# v2.net
KiCad netlist of a schematic drawn in EAGLE
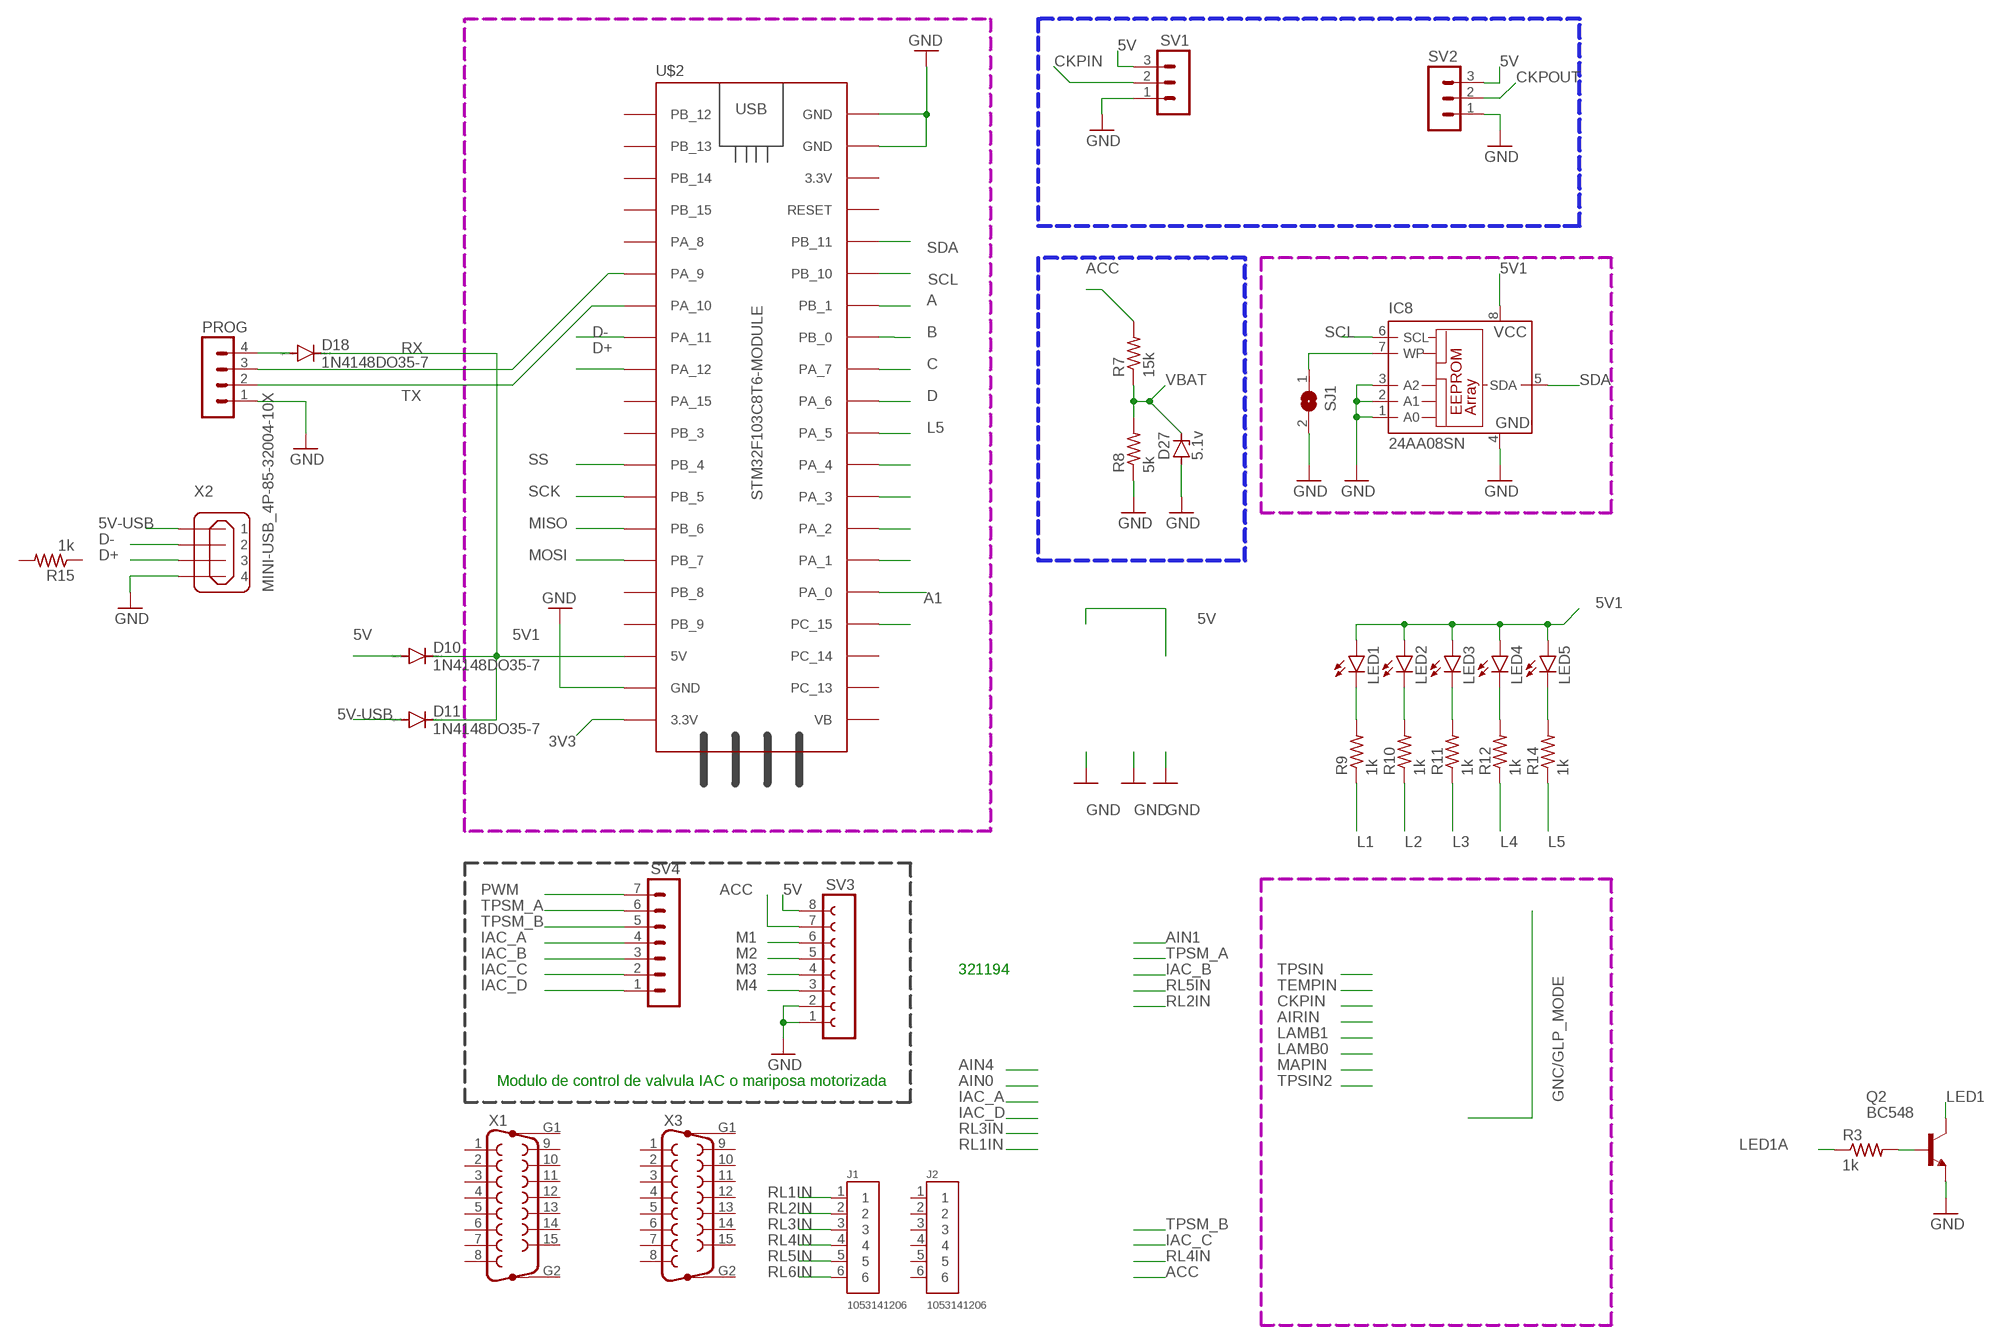
[diagram p0: schematic, sheet 1]
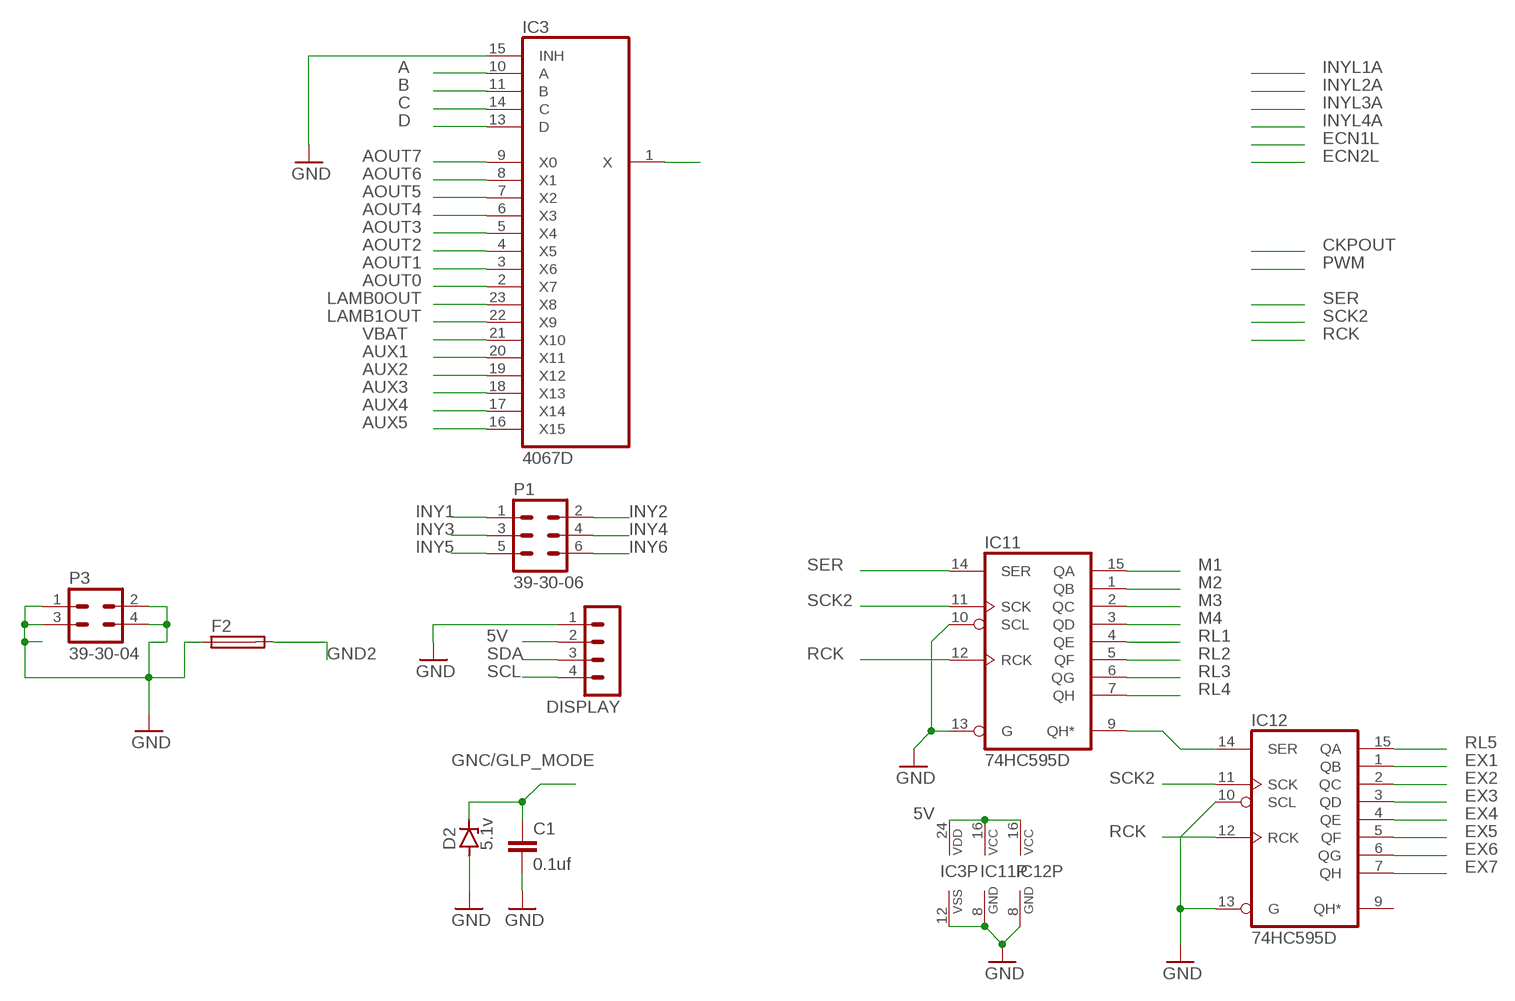
[diagram p1: schematic, sheet 2]
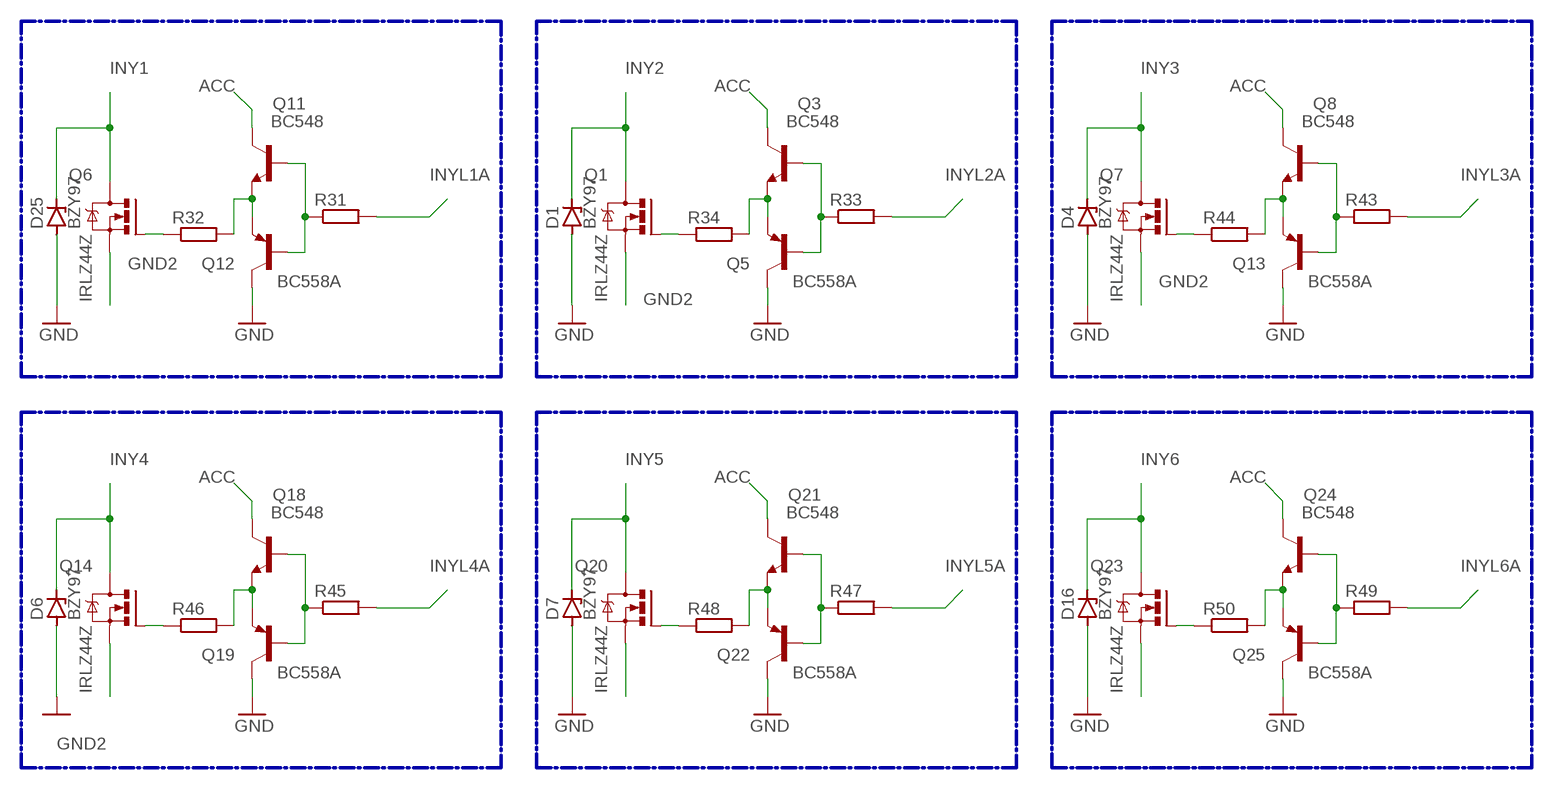
[diagram p2: schematic, sheet 3]
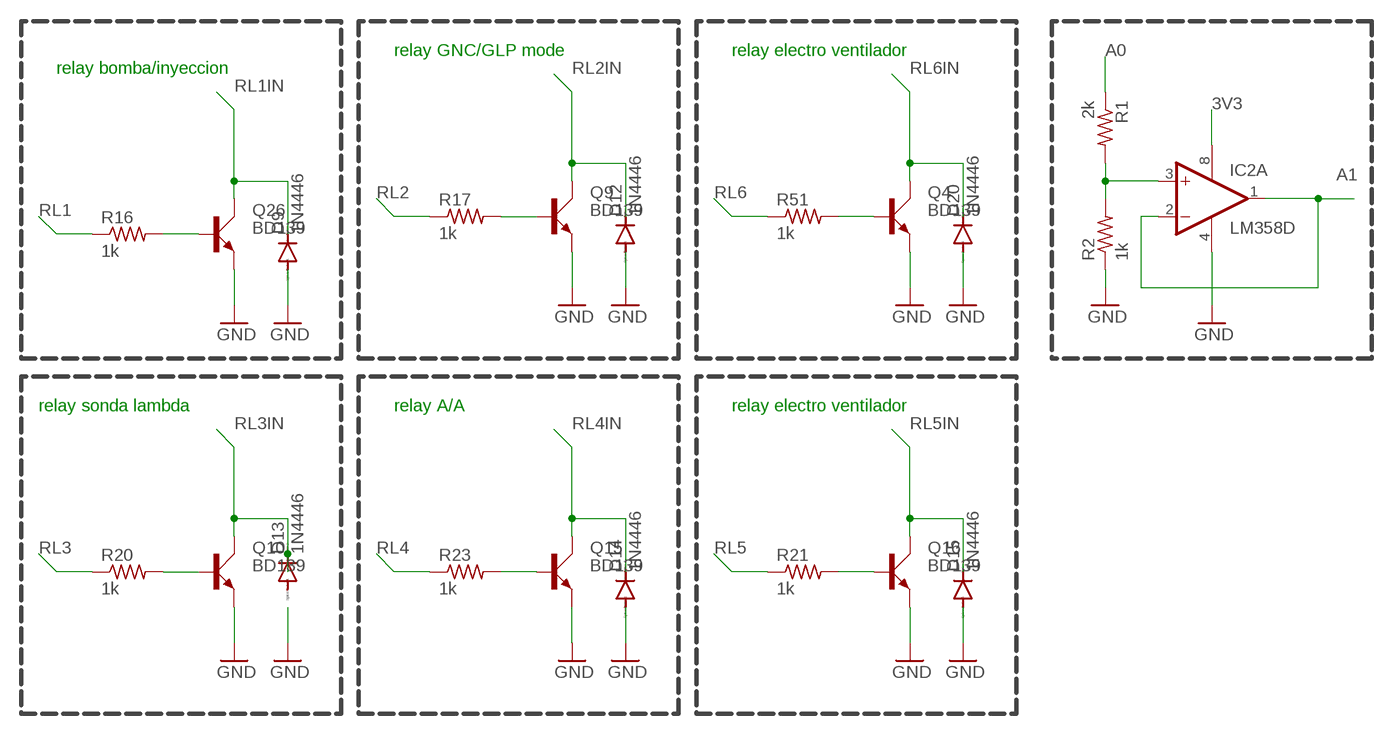
[diagram p3: schematic, sheet 4]
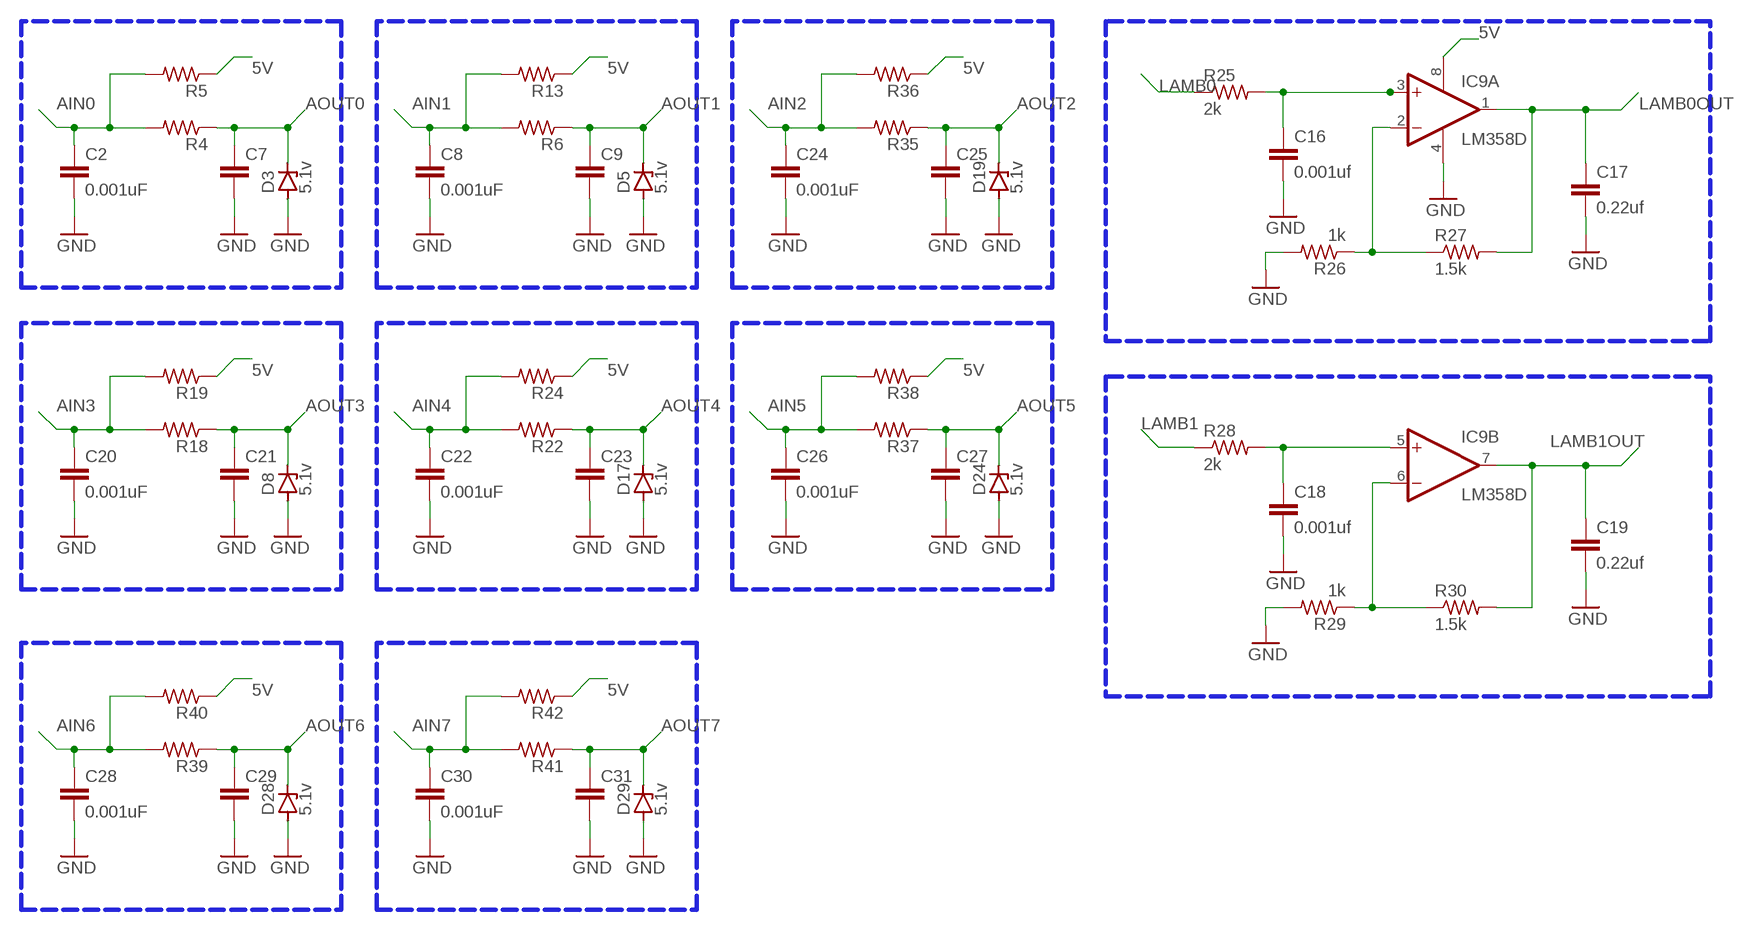
[diagram p4: schematic, sheet 5]

(export (version "E")
  (design (tool "Eeschema 10.0.6"))
  (components
    (comp (ref "D10")
      (value "1N4148DO35-7")
      (footprint "eagle-import:DO35-7")
      (libsource (lib "eagle-import") (part "1N4148DO35-7"))
    )
    (comp (ref "D11")
      (value "1N4148DO35-7")
      (footprint "eagle-import:DO35-7")
      (libsource (lib "eagle-import") (part "1N4148DO35-7"))
    )
    (comp (ref "D18")
      (value "1N4148DO35-7")
      (footprint "eagle-import:DO35-7")
      (libsource (lib "eagle-import") (part "1N4148DO35-7"))
    )
    (comp (ref "D27")
      (value "5.1v")
      (footprint "eagle-import:ZDIO-5")
      (libsource (lib "eagle-import") (part "ZENER-DIODEZD-5"))
    )
    (comp (ref "IC8")
      (value "24AA08SN")
      (footprint "eagle-import:SO-08")
      (fields (field (name "MF") "MICROCHIP") (field (name "MPN") "24AA08-I/SN"))
      (libsource (lib "eagle-import") (part "24SNAA08"))
    )
    (comp (ref "J1")
      (value "1053141206")
      (footprint "eagle-import:MOLEX_1053141206")
      (fields (field (name "MF") "Molex"))
      (libsource (lib "eagle-import") (part "1053141206"))
    )
    (comp (ref "J2")
      (value "1053141206")
      (footprint "eagle-import:MOLEX_1053141206")
      (fields (field (name "MF") "Molex"))
      (libsource (lib "eagle-import") (part "1053141206"))
    )
    (comp (ref "LED1")
      (value "LED3MM")
      (footprint "eagle-import:LED3MM")
      (libsource (lib "eagle-import") (part "LED3MM"))
    )
    (comp (ref "LED2")
      (value "LED3MM")
      (footprint "eagle-import:LED3MM")
      (libsource (lib "eagle-import") (part "LED3MM"))
    )
    (comp (ref "LED3")
      (value "LED3MM")
      (footprint "eagle-import:LED3MM")
      (libsource (lib "eagle-import") (part "LED3MM"))
    )
    (comp (ref "LED4")
      (value "LED3MM")
      (footprint "eagle-import:LED3MM")
      (libsource (lib "eagle-import") (part "LED3MM"))
    )
    (comp (ref "LED5")
      (value "LED3MM")
      (footprint "eagle-import:LED3MM")
      (libsource (lib "eagle-import") (part "LED3MM"))
    )
    (comp (ref "PROG")
      (value "MA04-1")
      (footprint "eagle-import:MA04-1")
      (libsource (lib "eagle-import") (part "MA04-1"))
    )
    (comp (ref "Q2")
      (value "BC548")
      (footprint "eagle-import:TO92-EBC")
      (libsource (lib "eagle-import") (part "BC548"))
    )
    (comp (ref "R3")
      (value "1k")
      (footprint "eagle-import:0204_5")
      (libsource (lib "eagle-import") (part "R-US_0204/5"))
    )
    (comp (ref "R7")
      (value "15k")
      (footprint "eagle-import:0204_5")
      (libsource (lib "eagle-import") (part "R-US_0204/5"))
    )
    (comp (ref "R8")
      (value "5k")
      (footprint "eagle-import:0204_5")
      (libsource (lib "eagle-import") (part "R-US_0204/5"))
    )
    (comp (ref "R9")
      (value "1k")
      (footprint "eagle-import:0204_5")
      (libsource (lib "eagle-import") (part "R-US_0204/5"))
    )
    (comp (ref "R10")
      (value "1k")
      (footprint "eagle-import:0204_5")
      (libsource (lib "eagle-import") (part "R-US_0204/5"))
    )
    (comp (ref "R11")
      (value "1k")
      (footprint "eagle-import:0204_5")
      (libsource (lib "eagle-import") (part "R-US_0204/5"))
    )
    (comp (ref "R12")
      (value "1k")
      (footprint "eagle-import:0204_5")
      (libsource (lib "eagle-import") (part "R-US_0204/5"))
    )
    (comp (ref "R14")
      (value "1k")
      (footprint "eagle-import:0204_5")
      (libsource (lib "eagle-import") (part "R-US_0204/5"))
    )
    (comp (ref "R15")
      (value "1k")
      (footprint "eagle-import:0204_5")
      (libsource (lib "eagle-import") (part "R-US_0204/5"))
    )
    (comp (ref "SJ1")
      (value "SJW")
      (footprint "eagle-import:SJW")
      (libsource (lib "eagle-import") (part "SJW"))
    )
    (comp (ref "SV1")
      (value "MA03-1")
      (footprint "eagle-import:MA03-1")
      (libsource (lib "eagle-import") (part "MA03-1"))
    )
    (comp (ref "SV2")
      (value "MA03-1")
      (footprint "eagle-import:MA03-1")
      (libsource (lib "eagle-import") (part "MA03-1"))
    )
    (comp (ref "SV3")
      (value "FE08-1")
      (footprint "eagle-import:FE08")
      (libsource (lib "eagle-import") (part "FE08-1"))
    )
    (comp (ref "SV4")
      (value "MA07-1")
      (footprint "eagle-import:MA07-1")
      (libsource (lib "eagle-import") (part "MA07-1"))
    )
    (comp (ref "U$2")
      (value "STM32F103C8T6-MODULE")
      (footprint "eagle-import:STM32F103C8T6-MODULE")
      (libsource (lib "eagle-import") (part "STM32F103C8T6-MODULE"))
    )
    (comp (ref "X1")
      (value "F15HP")
      (footprint "eagle-import:F15HP")
      (libsource (lib "eagle-import") (part "F15HP"))
    )
    (comp (ref "X2")
      (value "MINI-USB_4P-85-32004-10X")
      (footprint "eagle-import:85-32004-10X")
      (libsource (lib "eagle-import") (part "MINI-USB_4P-85-32004-10X"))
    )
    (comp (ref "X3")
      (value "F15HP")
      (footprint "eagle-import:F15HP")
      (libsource (lib "eagle-import") (part "F15HP"))
    )
    (comp (ref "C2")
      (value "0.001uF")
      (footprint "eagle-import:C025-025X050")
      (libsource (lib "eagle-import") (part "C-EU025-025X050"))
    )
    (comp (ref "C7")
      (value "C-EU025-025X050")
      (footprint "eagle-import:C025-025X050")
      (libsource (lib "eagle-import") (part "C-EU025-025X050"))
    )
    (comp (ref "C8")
      (value "0.001uF")
      (footprint "eagle-import:C025-025X050")
      (libsource (lib "eagle-import") (part "C-EU025-025X050"))
    )
    (comp (ref "C9")
      (value "C-EU025-025X050")
      (footprint "eagle-import:C025-025X050")
      (libsource (lib "eagle-import") (part "C-EU025-025X050"))
    )
    (comp (ref "C16")
      (value "0.001uf")
      (footprint "eagle-import:C025-025X050")
      (libsource (lib "eagle-import") (part "C-EU025-025X050"))
    )
    (comp (ref "C17")
      (value "0.22uf")
      (footprint "eagle-import:C025-025X050")
      (libsource (lib "eagle-import") (part "C-EU025-025X050"))
    )
    (comp (ref "C18")
      (value "0.001uf")
      (footprint "eagle-import:C025-025X050")
      (libsource (lib "eagle-import") (part "C-EU025-025X050"))
    )
    (comp (ref "C19")
      (value "0.22uf")
      (footprint "eagle-import:C025-025X050")
      (libsource (lib "eagle-import") (part "C-EU025-025X050"))
    )
    (comp (ref "C20")
      (value "0.001uF")
      (footprint "eagle-import:C025-025X050")
      (libsource (lib "eagle-import") (part "C-EU025-025X050"))
    )
    (comp (ref "C21")
      (value "C-EU025-025X050")
      (footprint "eagle-import:C025-025X050")
      (libsource (lib "eagle-import") (part "C-EU025-025X050"))
    )
    (comp (ref "C22")
      (value "0.001uF")
      (footprint "eagle-import:C025-025X050")
      (libsource (lib "eagle-import") (part "C-EU025-025X050"))
    )
    (comp (ref "C23")
      (value "C-EU025-025X050")
      (footprint "eagle-import:C025-025X050")
      (libsource (lib "eagle-import") (part "C-EU025-025X050"))
    )
    (comp (ref "C24")
      (value "0.001uF")
      (footprint "eagle-import:C025-025X050")
      (libsource (lib "eagle-import") (part "C-EU025-025X050"))
    )
    (comp (ref "C25")
      (value "C-EU025-025X050")
      (footprint "eagle-import:C025-025X050")
      (libsource (lib "eagle-import") (part "C-EU025-025X050"))
    )
    (comp (ref "C26")
      (value "0.001uF")
      (footprint "eagle-import:C025-025X050")
      (libsource (lib "eagle-import") (part "C-EU025-025X050"))
    )
    (comp (ref "C27")
      (value "C-EU025-025X050")
      (footprint "eagle-import:C025-025X050")
      (libsource (lib "eagle-import") (part "C-EU025-025X050"))
    )
    (comp (ref "C28")
      (value "0.001uF")
      (footprint "eagle-import:C025-025X050")
      (libsource (lib "eagle-import") (part "C-EU025-025X050"))
    )
    (comp (ref "C29")
      (value "C-EU025-025X050")
      (footprint "eagle-import:C025-025X050")
      (libsource (lib "eagle-import") (part "C-EU025-025X050"))
    )
    (comp (ref "C30")
      (value "0.001uF")
      (footprint "eagle-import:C025-025X050")
      (libsource (lib "eagle-import") (part "C-EU025-025X050"))
    )
    (comp (ref "C31")
      (value "C-EU025-025X050")
      (footprint "eagle-import:C025-025X050")
      (libsource (lib "eagle-import") (part "C-EU025-025X050"))
    )
    (comp (ref "D3")
      (value "5.1v")
      (footprint "eagle-import:ZDIO-5")
      (libsource (lib "eagle-import") (part "ZENER-DIODEZD-5"))
    )
    (comp (ref "D5")
      (value "5.1v")
      (footprint "eagle-import:ZDIO-5")
      (libsource (lib "eagle-import") (part "ZENER-DIODEZD-5"))
    )
    (comp (ref "D8")
      (value "5.1v")
      (footprint "eagle-import:ZDIO-5")
      (libsource (lib "eagle-import") (part "ZENER-DIODEZD-5"))
    )
    (comp (ref "D17")
      (value "5.1v")
      (footprint "eagle-import:ZDIO-5")
      (libsource (lib "eagle-import") (part "ZENER-DIODEZD-5"))
    )
    (comp (ref "D19")
      (value "5.1v")
      (footprint "eagle-import:ZDIO-5")
      (libsource (lib "eagle-import") (part "ZENER-DIODEZD-5"))
    )
    (comp (ref "D24")
      (value "5.1v")
      (footprint "eagle-import:ZDIO-5")
      (libsource (lib "eagle-import") (part "ZENER-DIODEZD-5"))
    )
    (comp (ref "D28")
      (value "5.1v")
      (footprint "eagle-import:ZDIO-5")
      (libsource (lib "eagle-import") (part "ZENER-DIODEZD-5"))
    )
    (comp (ref "D29")
      (value "5.1v")
      (footprint "eagle-import:ZDIO-5")
      (libsource (lib "eagle-import") (part "ZENER-DIODEZD-5"))
    )
    (comp (ref "IC9")
      (value "LM358D")
      (footprint "eagle-import:SO08")
      (libsource (lib "eagle-import") (part "LM358D"))
    )
    (comp (ref "R4")
      (value "R-US_0204/5")
      (footprint "eagle-import:0204_5")
      (libsource (lib "eagle-import") (part "R-US_0204/5"))
    )
    (comp (ref "R5")
      (value "R-US_0204/5")
      (footprint "eagle-import:0204_5")
      (libsource (lib "eagle-import") (part "R-US_0204/5"))
    )
    (comp (ref "R6")
      (value "R-US_0204/5")
      (footprint "eagle-import:0204_5")
      (libsource (lib "eagle-import") (part "R-US_0204/5"))
    )
    (comp (ref "R13")
      (value "R-US_0204/5")
      (footprint "eagle-import:0204_5")
      (libsource (lib "eagle-import") (part "R-US_0204/5"))
    )
    (comp (ref "R18")
      (value "R-US_0204/5")
      (footprint "eagle-import:0204_5")
      (libsource (lib "eagle-import") (part "R-US_0204/5"))
    )
    (comp (ref "R19")
      (value "R-US_0204/5")
      (footprint "eagle-import:0204_5")
      (libsource (lib "eagle-import") (part "R-US_0204/5"))
    )
    (comp (ref "R22")
      (value "R-US_0204/5")
      (footprint "eagle-import:0204_5")
      (libsource (lib "eagle-import") (part "R-US_0204/5"))
    )
    (comp (ref "R24")
      (value "R-US_0204/5")
      (footprint "eagle-import:0204_5")
      (libsource (lib "eagle-import") (part "R-US_0204/5"))
    )
    (comp (ref "R25")
      (value "2k")
      (footprint "eagle-import:0204_5")
      (libsource (lib "eagle-import") (part "R-US_0204/5"))
    )
    (comp (ref "R26")
      (value "1k")
      (footprint "eagle-import:0204_5")
      (libsource (lib "eagle-import") (part "R-US_0204/5"))
    )
    (comp (ref "R27")
      (value "1.5k")
      (footprint "eagle-import:0204_5")
      (libsource (lib "eagle-import") (part "R-US_0204/5"))
    )
    (comp (ref "R28")
      (value "2k")
      (footprint "eagle-import:0204_5")
      (libsource (lib "eagle-import") (part "R-US_0204/5"))
    )
    (comp (ref "R29")
      (value "1k")
      (footprint "eagle-import:0204_5")
      (libsource (lib "eagle-import") (part "R-US_0204/5"))
    )
    (comp (ref "R30")
      (value "1.5k")
      (footprint "eagle-import:0204_5")
      (libsource (lib "eagle-import") (part "R-US_0204/5"))
    )
    (comp (ref "R35")
      (value "R-US_0204/5")
      (footprint "eagle-import:0204_5")
      (libsource (lib "eagle-import") (part "R-US_0204/5"))
    )
    (comp (ref "R36")
      (value "R-US_0204/5")
      (footprint "eagle-import:0204_5")
      (libsource (lib "eagle-import") (part "R-US_0204/5"))
    )
    (comp (ref "R37")
      (value "R-US_0204/5")
      (footprint "eagle-import:0204_5")
      (libsource (lib "eagle-import") (part "R-US_0204/5"))
    )
    (comp (ref "R38")
      (value "R-US_0204/5")
      (footprint "eagle-import:0204_5")
      (libsource (lib "eagle-import") (part "R-US_0204/5"))
    )
    (comp (ref "R39")
      (value "R-US_0204/5")
      (footprint "eagle-import:0204_5")
      (libsource (lib "eagle-import") (part "R-US_0204/5"))
    )
    (comp (ref "R40")
      (value "R-US_0204/5")
      (footprint "eagle-import:0204_5")
      (libsource (lib "eagle-import") (part "R-US_0204/5"))
    )
    (comp (ref "R41")
      (value "R-US_0204/5")
      (footprint "eagle-import:0204_5")
      (libsource (lib "eagle-import") (part "R-US_0204/5"))
    )
    (comp (ref "R42")
      (value "R-US_0204/5")
      (footprint "eagle-import:0204_5")
      (libsource (lib "eagle-import") (part "R-US_0204/5"))
    )
    (comp (ref "D9")
      (value "1N4446")
      (footprint "eagle-import:DO35-10")
      (libsource (lib "eagle-import") (part "1N4446"))
    )
    (comp (ref "D12")
      (value "1N4446")
      (footprint "eagle-import:DO35-10")
      (libsource (lib "eagle-import") (part "1N4446"))
    )
    (comp (ref "D13")
      (value "1N4446")
      (footprint "eagle-import:DO35-10")
      (libsource (lib "eagle-import") (part "1N4446"))
    )
    (comp (ref "D14")
      (value "1N4446")
      (footprint "eagle-import:DO35-10")
      (libsource (lib "eagle-import") (part "1N4446"))
    )
    (comp (ref "D15")
      (value "1N4446")
      (footprint "eagle-import:DO35-10")
      (libsource (lib "eagle-import") (part "1N4446"))
    )
    (comp (ref "D20")
      (value "1N4446")
      (footprint "eagle-import:DO35-10")
      (libsource (lib "eagle-import") (part "1N4446"))
    )
    (comp (ref "IC2")
      (value "LM358D")
      (footprint "eagle-import:SO08")
      (libsource (lib "eagle-import") (part "LM358D"))
    )
    (comp (ref "Q4")
      (value "BD139")
      (footprint "eagle-import:TO126AV")
      (libsource (lib "eagle-import") (part "BD139"))
    )
    (comp (ref "Q9")
      (value "BD139")
      (footprint "eagle-import:TO126AV")
      (libsource (lib "eagle-import") (part "BD139"))
    )
    (comp (ref "Q10")
      (value "BD139")
      (footprint "eagle-import:TO126AV")
      (libsource (lib "eagle-import") (part "BD139"))
    )
    (comp (ref "Q15")
      (value "BD139")
      (footprint "eagle-import:TO126AV")
      (libsource (lib "eagle-import") (part "BD139"))
    )
    (comp (ref "Q16")
      (value "BD139")
      (footprint "eagle-import:TO126AV")
      (libsource (lib "eagle-import") (part "BD139"))
    )
    (comp (ref "Q26")
      (value "BD139")
      (footprint "eagle-import:TO126AV")
      (libsource (lib "eagle-import") (part "BD139"))
    )
    (comp (ref "R1")
      (value "2k")
      (footprint "eagle-import:0204_5")
      (libsource (lib "eagle-import") (part "R-US_0204/5"))
    )
    (comp (ref "R2")
      (value "1k")
      (footprint "eagle-import:0204_5")
      (libsource (lib "eagle-import") (part "R-US_0204/5"))
    )
    (comp (ref "R16")
      (value "1k")
      (footprint "eagle-import:0204_5")
      (libsource (lib "eagle-import") (part "R-US_0204/5"))
    )
    (comp (ref "R17")
      (value "1k")
      (footprint "eagle-import:0204_5")
      (libsource (lib "eagle-import") (part "R-US_0204/5"))
    )
    (comp (ref "R20")
      (value "1k")
      (footprint "eagle-import:0204_5")
      (libsource (lib "eagle-import") (part "R-US_0204/5"))
    )
    (comp (ref "R21")
      (value "1k")
      (footprint "eagle-import:0204_5")
      (libsource (lib "eagle-import") (part "R-US_0204/5"))
    )
    (comp (ref "R23")
      (value "1k")
      (footprint "eagle-import:0204_5")
      (libsource (lib "eagle-import") (part "R-US_0204/5"))
    )
    (comp (ref "R51")
      (value "1k")
      (footprint "eagle-import:0204_5")
      (libsource (lib "eagle-import") (part "R-US_0204/5"))
    )
    (comp (ref "D1")
      (value "BZY97")
      (footprint "eagle-import:F126Z12")
      (libsource (lib "eagle-import") (part "BZY97"))
    )
    (comp (ref "D4")
      (value "BZY97")
      (footprint "eagle-import:F126Z12")
      (libsource (lib "eagle-import") (part "BZY97"))
    )
    (comp (ref "D6")
      (value "BZY97")
      (footprint "eagle-import:F126Z12")
      (libsource (lib "eagle-import") (part "BZY97"))
    )
    (comp (ref "D7")
      (value "BZY97")
      (footprint "eagle-import:F126Z12")
      (libsource (lib "eagle-import") (part "BZY97"))
    )
    (comp (ref "D16")
      (value "BZY97")
      (footprint "eagle-import:F126Z12")
      (libsource (lib "eagle-import") (part "BZY97"))
    )
    (comp (ref "D25")
      (value "BZY97")
      (footprint "eagle-import:F126Z12")
      (libsource (lib "eagle-import") (part "BZY97"))
    )
    (comp (ref "Q1")
      (value "IRLZ44Z")
      (footprint "eagle-import:TO220BH")
      (libsource (lib "eagle-import") (part "IRLZ44Z"))
    )
    (comp (ref "Q3")
      (value "BC548")
      (footprint "eagle-import:TO92-EBC")
      (libsource (lib "eagle-import") (part "BC548"))
    )
    (comp (ref "Q5")
      (value "BC558A")
      (footprint "eagle-import:TO92-EBC")
      (libsource (lib "eagle-import") (part "BC558A"))
    )
    (comp (ref "Q6")
      (value "IRLZ44Z")
      (footprint "eagle-import:TO220BH")
      (libsource (lib "eagle-import") (part "IRLZ44Z"))
    )
    (comp (ref "Q7")
      (value "IRLZ44Z")
      (footprint "eagle-import:TO220BH")
      (libsource (lib "eagle-import") (part "IRLZ44Z"))
    )
    (comp (ref "Q8")
      (value "BC548")
      (footprint "eagle-import:TO92-EBC")
      (libsource (lib "eagle-import") (part "BC548"))
    )
    (comp (ref "Q11")
      (value "BC548")
      (footprint "eagle-import:TO92-EBC")
      (libsource (lib "eagle-import") (part "BC548"))
    )
    (comp (ref "Q12")
      (value "BC558A")
      (footprint "eagle-import:TO92-EBC")
      (libsource (lib "eagle-import") (part "BC558A"))
    )
    (comp (ref "Q13")
      (value "BC558A")
      (footprint "eagle-import:TO92-EBC")
      (libsource (lib "eagle-import") (part "BC558A"))
    )
    (comp (ref "Q14")
      (value "IRLZ44Z")
      (footprint "eagle-import:TO220BH")
      (libsource (lib "eagle-import") (part "IRLZ44Z"))
    )
    (comp (ref "Q18")
      (value "BC548")
      (footprint "eagle-import:TO92-EBC")
      (libsource (lib "eagle-import") (part "BC548"))
    )
    (comp (ref "Q19")
      (value "BC558A")
      (footprint "eagle-import:TO92-EBC")
      (libsource (lib "eagle-import") (part "BC558A"))
    )
    (comp (ref "Q20")
      (value "IRLZ44Z")
      (footprint "eagle-import:TO220BH")
      (libsource (lib "eagle-import") (part "IRLZ44Z"))
    )
    (comp (ref "Q21")
      (value "BC548")
      (footprint "eagle-import:TO92-EBC")
      (libsource (lib "eagle-import") (part "BC548"))
    )
    (comp (ref "Q22")
      (value "BC558A")
      (footprint "eagle-import:TO92-EBC")
      (libsource (lib "eagle-import") (part "BC558A"))
    )
    (comp (ref "Q23")
      (value "IRLZ44Z")
      (footprint "eagle-import:TO220BH")
      (libsource (lib "eagle-import") (part "IRLZ44Z"))
    )
    (comp (ref "Q24")
      (value "BC548")
      (footprint "eagle-import:TO92-EBC")
      (libsource (lib "eagle-import") (part "BC548"))
    )
    (comp (ref "Q25")
      (value "BC558A")
      (footprint "eagle-import:TO92-EBC")
      (libsource (lib "eagle-import") (part "BC558A"))
    )
    (comp (ref "R31")
      (value "R-EU_0207/10")
      (footprint "eagle-import:0207_10")
      (libsource (lib "eagle-import") (part "R-EU_0207/10"))
    )
    (comp (ref "R32")
      (value "R-EU_0207/10")
      (footprint "eagle-import:0207_10")
      (libsource (lib "eagle-import") (part "R-EU_0207/10"))
    )
    (comp (ref "R33")
      (value "R-EU_0207/10")
      (footprint "eagle-import:0207_10")
      (libsource (lib "eagle-import") (part "R-EU_0207/10"))
    )
    (comp (ref "R34")
      (value "R-EU_0207/10")
      (footprint "eagle-import:0207_10")
      (libsource (lib "eagle-import") (part "R-EU_0207/10"))
    )
    (comp (ref "R43")
      (value "R-EU_0207/10")
      (footprint "eagle-import:0207_10")
      (libsource (lib "eagle-import") (part "R-EU_0207/10"))
    )
    (comp (ref "R44")
      (value "R-EU_0207/10")
      (footprint "eagle-import:0207_10")
      (libsource (lib "eagle-import") (part "R-EU_0207/10"))
    )
    (comp (ref "R45")
      (value "R-EU_0207/10")
      (footprint "eagle-import:0207_10")
      (libsource (lib "eagle-import") (part "R-EU_0207/10"))
    )
    (comp (ref "R46")
      (value "R-EU_0207/10")
      (footprint "eagle-import:0207_10")
      (libsource (lib "eagle-import") (part "R-EU_0207/10"))
    )
    (comp (ref "R47")
      (value "R-EU_0207/10")
      (footprint "eagle-import:0207_10")
      (libsource (lib "eagle-import") (part "R-EU_0207/10"))
    )
    (comp (ref "R48")
      (value "R-EU_0207/10")
      (footprint "eagle-import:0207_10")
      (libsource (lib "eagle-import") (part "R-EU_0207/10"))
    )
    (comp (ref "R49")
      (value "R-EU_0207/10")
      (footprint "eagle-import:0207_10")
      (libsource (lib "eagle-import") (part "R-EU_0207/10"))
    )
    (comp (ref "R50")
      (value "R-EU_0207/10")
      (footprint "eagle-import:0207_10")
      (libsource (lib "eagle-import") (part "R-EU_0207/10"))
    )
    (comp (ref "C1")
      (value "0.1uf")
      (footprint "eagle-import:C025-025X050")
      (libsource (lib "eagle-import") (part "C-EU025-025X050"))
    )
    (comp (ref "D2")
      (value "5.1v")
      (footprint "eagle-import:ZDIO-5")
      (libsource (lib "eagle-import") (part "ZENER-DIODEZD-5"))
    )
    (comp (ref "DISPLAY")
      (value "MA04-1")
      (footprint "eagle-import:MA04-1")
      (libsource (lib "eagle-import") (part "MA04-1"))
    )
    (comp (ref "F2")
      (value "TE5")
      (footprint "eagle-import:TE5")
      (libsource (lib "eagle-import") (part "TE5"))
    )
    (comp (ref "IC3")
      (value "4067D")
      (footprint "eagle-import:SO24W")
      (libsource (lib "eagle-import") (part "4067D"))
    )
    (comp (ref "IC11")
      (value "74HC595D")
      (footprint "eagle-import:SO16")
      (libsource (lib "eagle-import") (part "74595DHC"))
    )
    (comp (ref "IC12")
      (value "74HC595D")
      (footprint "eagle-import:SO16")
      (libsource (lib "eagle-import") (part "74595DHC"))
    )
    (comp (ref "P1")
      (value "39-30-06")
      (footprint "eagle-import:39-30-_06_")
      (libsource (lib "eagle-import") (part "39-30-?06?"))
    )
    (comp (ref "P3")
      (value "39-30-04")
      (footprint "eagle-import:39-30-_04_")
      (libsource (lib "eagle-import") (part "39-30-?04?"))
    )
  )
  (nets
    (net (code "3") (name "3V3") (class "Default")
      (node (ref "IC2") (pin "8") (pinfunction "V+_8") (pintype "power_in"))
      (node (ref "U$2") (pin "3.3V_1") (pinfunction "3.3V_3.3V_1") (pintype "bidirectional"))
    )
    (net (code "4") (name "5V") (class "Default")
      (node (ref "D10") (pin "A") (pinfunction "A_A") (pintype "passive"))
      (node (ref "DISPLAY") (pin "2") (pinfunction "2_2") (pintype "passive"))
      (node (ref "IC11") (pin "16") (pinfunction "VCC_16") (pintype "power_in"))
      (node (ref "IC12") (pin "16") (pinfunction "VCC_16") (pintype "power_in"))
      (node (ref "IC3") (pin "24") (pinfunction "VDD_24") (pintype "power_in"))
      (node (ref "IC9") (pin "8") (pinfunction "V+_8") (pintype "power_in"))
      (node (ref "R13") (pin "1") (pinfunction "1_1") (pintype "passive"))
      (node (ref "R19") (pin "1") (pinfunction "1_1") (pintype "passive"))
      (node (ref "R24") (pin "1") (pinfunction "1_1") (pintype "passive"))
      (node (ref "R36") (pin "1") (pinfunction "1_1") (pintype "passive"))
      (node (ref "R38") (pin "1") (pinfunction "1_1") (pintype "passive"))
      (node (ref "R40") (pin "1") (pinfunction "1_1") (pintype "passive"))
      (node (ref "R42") (pin "1") (pinfunction "1_1") (pintype "passive"))
      (node (ref "R5") (pin "1") (pinfunction "1_1") (pintype "passive"))
      (node (ref "SV1") (pin "3") (pinfunction "3_3") (pintype "passive"))
      (node (ref "SV2") (pin "3") (pinfunction "3_3") (pintype "passive"))
      (node (ref "SV3") (pin "8") (pinfunction "8_8") (pintype "passive"))
    )
    (net (code "5") (name "5V-USB") (class "Default")
      (node (ref "D11") (pin "A") (pinfunction "A_A") (pintype "passive"))
      (node (ref "X2") (pin "1") (pinfunction "1_1") (pintype "passive"))
    )
    (net (code "6") (name "5V1") (class "Default")
      (node (ref "D10") (pin "C") (pinfunction "C_C") (pintype "passive"))
      (node (ref "D11") (pin "C") (pinfunction "C_C") (pintype "passive"))
      (node (ref "D18") (pin "C") (pinfunction "C_C") (pintype "passive"))
      (node (ref "IC8") (pin "8") (pinfunction "VCC_8") (pintype "power_in"))
      (node (ref "LED1") (pin "A") (pinfunction "A_A") (pintype "passive"))
      (node (ref "LED2") (pin "A") (pinfunction "A_A") (pintype "passive"))
      (node (ref "LED3") (pin "A") (pinfunction "A_A") (pintype "passive"))
      (node (ref "LED4") (pin "A") (pinfunction "A_A") (pintype "passive"))
      (node (ref "LED5") (pin "A") (pinfunction "A_A") (pintype "passive"))
      (node (ref "U$2") (pin "5V") (pinfunction "5V_5V") (pintype "bidirectional"))
    )
    (net (code "7") (name "A") (class "Default")
      (node (ref "IC3") (pin "10") (pinfunction "A_10") (pintype "input"))
      (node (ref "U$2") (pin "PB_1") (pinfunction "PB_1_PB_1") (pintype "bidirectional"))
    )
    (net (code "8") (name "A0") (class "Default")
      (node (ref "IC3") (pin "1") (pinfunction "X_1") (pintype "output"))
      (node (ref "R1") (pin "1") (pinfunction "1_1") (pintype "passive"))
    )
    (net (code "9") (name "A1") (class "Default")
      (node (ref "IC2") (pin "1") (pinfunction "OUT_1") (pintype "output"))
      (node (ref "IC2") (pin "2") (pinfunction "-IN_2") (pintype "input"))
      (node (ref "U$2") (pin "PA_0") (pinfunction "PA_0_PA_0") (pintype "bidirectional"))
    )
    (net (code "10") (name "ACC") (class "Default")
      (node (ref "Q11") (pin "C") (pinfunction "C_C") (pintype "passive"))
      (node (ref "Q18") (pin "C") (pinfunction "C_C") (pintype "passive"))
      (node (ref "Q21") (pin "C") (pinfunction "C_C") (pintype "passive"))
      (node (ref "Q24") (pin "C") (pinfunction "C_C") (pintype "passive"))
      (node (ref "Q3") (pin "C") (pinfunction "C_C") (pintype "passive"))
      (node (ref "Q8") (pin "C") (pinfunction "C_C") (pintype "passive"))
      (node (ref "R7") (pin "2") (pinfunction "2_2") (pintype "passive"))
      (node (ref "SV3") (pin "7") (pinfunction "7_7") (pintype "passive"))
    )
    (net (code "11") (name "AIN0") (class "Default")
      (node (ref "C2") (pin "1") (pinfunction "1_1") (pintype "passive"))
      (node (ref "R4") (pin "2") (pinfunction "2_2") (pintype "passive"))
      (node (ref "R5") (pin "2") (pinfunction "2_2") (pintype "passive"))
    )
    (net (code "12") (name "AIN1") (class "Default")
      (node (ref "C8") (pin "1") (pinfunction "1_1") (pintype "passive"))
      (node (ref "R13") (pin "2") (pinfunction "2_2") (pintype "passive"))
      (node (ref "R6") (pin "2") (pinfunction "2_2") (pintype "passive"))
    )
    (net (code "13") (name "AIN2") (class "Default")
      (node (ref "C24") (pin "1") (pinfunction "1_1") (pintype "passive"))
      (node (ref "R35") (pin "2") (pinfunction "2_2") (pintype "passive"))
      (node (ref "R36") (pin "2") (pinfunction "2_2") (pintype "passive"))
    )
    (net (code "14") (name "AIN3") (class "Default")
      (node (ref "C20") (pin "1") (pinfunction "1_1") (pintype "passive"))
      (node (ref "R18") (pin "2") (pinfunction "2_2") (pintype "passive"))
      (node (ref "R19") (pin "2") (pinfunction "2_2") (pintype "passive"))
    )
    (net (code "15") (name "AIN4") (class "Default")
      (node (ref "C22") (pin "1") (pinfunction "1_1") (pintype "passive"))
      (node (ref "R22") (pin "2") (pinfunction "2_2") (pintype "passive"))
      (node (ref "R24") (pin "2") (pinfunction "2_2") (pintype "passive"))
    )
    (net (code "16") (name "AIN5") (class "Default")
      (node (ref "C26") (pin "1") (pinfunction "1_1") (pintype "passive"))
      (node (ref "R37") (pin "2") (pinfunction "2_2") (pintype "passive"))
      (node (ref "R38") (pin "2") (pinfunction "2_2") (pintype "passive"))
    )
    (net (code "17") (name "AIN6") (class "Default")
      (node (ref "C28") (pin "1") (pinfunction "1_1") (pintype "passive"))
      (node (ref "R39") (pin "2") (pinfunction "2_2") (pintype "passive"))
      (node (ref "R40") (pin "2") (pinfunction "2_2") (pintype "passive"))
    )
    (net (code "18") (name "AIN7") (class "Default")
      (node (ref "C30") (pin "1") (pinfunction "1_1") (pintype "passive"))
      (node (ref "R41") (pin "2") (pinfunction "2_2") (pintype "passive"))
      (node (ref "R42") (pin "2") (pinfunction "2_2") (pintype "passive"))
    )
    (net (code "20") (name "AOUT0") (class "Default")
      (node (ref "C7") (pin "1") (pinfunction "1_1") (pintype "passive"))
      (node (ref "D3") (pin "C") (pinfunction "C_C") (pintype "passive"))
      (node (ref "IC3") (pin "2") (pinfunction "X7_2") (pintype "input"))
      (node (ref "R4") (pin "1") (pinfunction "1_1") (pintype "passive"))
    )
    (net (code "21") (name "AOUT1") (class "Default")
      (node (ref "C9") (pin "1") (pinfunction "1_1") (pintype "passive"))
      (node (ref "D5") (pin "C") (pinfunction "C_C") (pintype "passive"))
      (node (ref "IC3") (pin "3") (pinfunction "X6_3") (pintype "input"))
      (node (ref "R6") (pin "1") (pinfunction "1_1") (pintype "passive"))
    )
    (net (code "22") (name "AOUT2") (class "Default")
      (node (ref "C25") (pin "1") (pinfunction "1_1") (pintype "passive"))
      (node (ref "D19") (pin "C") (pinfunction "C_C") (pintype "passive"))
      (node (ref "IC3") (pin "4") (pinfunction "X5_4") (pintype "input"))
      (node (ref "R35") (pin "1") (pinfunction "1_1") (pintype "passive"))
    )
    (net (code "23") (name "AOUT3") (class "Default")
      (node (ref "C21") (pin "1") (pinfunction "1_1") (pintype "passive"))
      (node (ref "D8") (pin "C") (pinfunction "C_C") (pintype "passive"))
      (node (ref "IC3") (pin "5") (pinfunction "X4_5") (pintype "input"))
      (node (ref "R18") (pin "1") (pinfunction "1_1") (pintype "passive"))
    )
    (net (code "24") (name "AOUT4") (class "Default")
      (node (ref "C23") (pin "1") (pinfunction "1_1") (pintype "passive"))
      (node (ref "D17") (pin "C") (pinfunction "C_C") (pintype "passive"))
      (node (ref "IC3") (pin "6") (pinfunction "X3_6") (pintype "input"))
      (node (ref "R22") (pin "1") (pinfunction "1_1") (pintype "passive"))
    )
    (net (code "25") (name "AOUT5") (class "Default")
      (node (ref "C27") (pin "1") (pinfunction "1_1") (pintype "passive"))
      (node (ref "D24") (pin "C") (pinfunction "C_C") (pintype "passive"))
      (node (ref "IC3") (pin "7") (pinfunction "X2_7") (pintype "input"))
      (node (ref "R37") (pin "1") (pinfunction "1_1") (pintype "passive"))
    )
    (net (code "26") (name "AOUT6") (class "Default")
      (node (ref "C29") (pin "1") (pinfunction "1_1") (pintype "passive"))
      (node (ref "D28") (pin "C") (pinfunction "C_C") (pintype "passive"))
      (node (ref "IC3") (pin "8") (pinfunction "X1_8") (pintype "input"))
      (node (ref "R39") (pin "1") (pinfunction "1_1") (pintype "passive"))
    )
    (net (code "27") (name "AOUT7") (class "Default")
      (node (ref "C31") (pin "1") (pinfunction "1_1") (pintype "passive"))
      (node (ref "D29") (pin "C") (pinfunction "C_C") (pintype "passive"))
      (node (ref "IC3") (pin "9") (pinfunction "X0_9") (pintype "input"))
      (node (ref "R41") (pin "1") (pinfunction "1_1") (pintype "passive"))
    )
    (net (code "28") (name "AUX1") (class "Default")
      (node (ref "IC3") (pin "20") (pinfunction "X11_20") (pintype "input"))
    )
    (net (code "29") (name "AUX2") (class "Default")
      (node (ref "IC3") (pin "19") (pinfunction "X12_19") (pintype "input"))
    )
    (net (code "30") (name "AUX3") (class "Default")
      (node (ref "IC3") (pin "18") (pinfunction "X13_18") (pintype "input"))
    )
    (net (code "31") (name "AUX4") (class "Default")
      (node (ref "IC3") (pin "17") (pinfunction "X14_17") (pintype "input"))
    )
    (net (code "32") (name "AUX5") (class "Default")
      (node (ref "IC3") (pin "16") (pinfunction "X15_16") (pintype "input"))
    )
    (net (code "33") (name "B") (class "Default")
      (node (ref "IC3") (pin "11") (pinfunction "B_11") (pintype "input"))
      (node (ref "U$2") (pin "PB_0") (pinfunction "PB_0_PB_0") (pintype "bidirectional"))
    )
    (net (code "34") (name "C") (class "Default")
      (node (ref "IC3") (pin "14") (pinfunction "C_14") (pintype "input"))
      (node (ref "U$2") (pin "PA_7") (pinfunction "PA_7_PA_7") (pintype "bidirectional"))
    )
    (net (code "35") (name "CKPIN") (class "Default")
      (node (ref "SV1") (pin "2") (pinfunction "2_2") (pintype "passive"))
    )
    (net (code "36") (name "CKPOUT") (class "Default")
      (node (ref "SV2") (pin "2") (pinfunction "2_2") (pintype "passive"))
    )
    (net (code "37") (name "D") (class "Default")
      (node (ref "IC3") (pin "13") (pinfunction "D_13") (pintype "input"))
      (node (ref "U$2") (pin "PA_6") (pinfunction "PA_6_PA_6") (pintype "bidirectional"))
    )
    (net (code "38") (name "D+") (class "Default")
      (node (ref "U$2") (pin "PA_12") (pinfunction "PA_12_PA_12") (pintype "bidirectional"))
      (node (ref "X2") (pin "3") (pinfunction "3_3") (pintype "passive"))
    )
    (net (code "39") (name "D-") (class "Default")
      (node (ref "U$2") (pin "PA_11") (pinfunction "PA_11_PA_11") (pintype "bidirectional"))
      (node (ref "X2") (pin "2") (pinfunction "2_2") (pintype "passive"))
    )
    (net (code "42") (name "EX1") (class "Default")
      (node (ref "IC12") (pin "1") (pinfunction "QB_1") (pintype "tri_state"))
    )
    (net (code "43") (name "EX2") (class "Default")
      (node (ref "IC12") (pin "2") (pinfunction "QC_2") (pintype "tri_state"))
    )
    (net (code "44") (name "EX3") (class "Default")
      (node (ref "IC12") (pin "3") (pinfunction "QD_3") (pintype "tri_state"))
    )
    (net (code "45") (name "EX4") (class "Default")
      (node (ref "IC12") (pin "4") (pinfunction "QE_4") (pintype "tri_state"))
    )
    (net (code "46") (name "EX5") (class "Default")
      (node (ref "IC12") (pin "5") (pinfunction "QF_5") (pintype "tri_state"))
    )
    (net (code "47") (name "EX6") (class "Default")
      (node (ref "IC12") (pin "6") (pinfunction "QG_6") (pintype "tri_state"))
    )
    (net (code "48") (name "EX7") (class "Default")
      (node (ref "IC12") (pin "7") (pinfunction "QH_7") (pintype "tri_state"))
    )
    (net (code "49") (name "GNC{slash}GLP_MODE") (class "Default")
      (node (ref "C1") (pin "1") (pinfunction "1_1") (pintype "passive"))
      (node (ref "D2") (pin "C") (pinfunction "C_C") (pintype "passive"))
    )
    (net (code "50") (name "GND") (class "Default")
      (node (ref "C1") (pin "2") (pinfunction "2_2") (pintype "passive"))
      (node (ref "C16") (pin "2") (pinfunction "2_2") (pintype "passive"))
      (node (ref "C17") (pin "2") (pinfunction "2_2") (pintype "passive"))
      (node (ref "C18") (pin "2") (pinfunction "2_2") (pintype "passive"))
      (node (ref "C19") (pin "2") (pinfunction "2_2") (pintype "passive"))
      (node (ref "C2") (pin "2") (pinfunction "2_2") (pintype "passive"))
      (node (ref "C20") (pin "2") (pinfunction "2_2") (pintype "passive"))
      (node (ref "C21") (pin "2") (pinfunction "2_2") (pintype "passive"))
      (node (ref "C22") (pin "2") (pinfunction "2_2") (pintype "passive"))
      (node (ref "C23") (pin "2") (pinfunction "2_2") (pintype "passive"))
      (node (ref "C24") (pin "2") (pinfunction "2_2") (pintype "passive"))
      (node (ref "C25") (pin "2") (pinfunction "2_2") (pintype "passive"))
      (node (ref "C26") (pin "2") (pinfunction "2_2") (pintype "passive"))
      (node (ref "C27") (pin "2") (pinfunction "2_2") (pintype "passive"))
      (node (ref "C28") (pin "2") (pinfunction "2_2") (pintype "passive"))
      (node (ref "C29") (pin "2") (pinfunction "2_2") (pintype "passive"))
      (node (ref "C30") (pin "2") (pinfunction "2_2") (pintype "passive"))
      (node (ref "C31") (pin "2") (pinfunction "2_2") (pintype "passive"))
      (node (ref "C7") (pin "2") (pinfunction "2_2") (pintype "passive"))
      (node (ref "C8") (pin "2") (pinfunction "2_2") (pintype "passive"))
      (node (ref "C9") (pin "2") (pinfunction "2_2") (pintype "passive"))
      (node (ref "D1") (pin "A") (pinfunction "A_A") (pintype "passive"))
      (node (ref "D12") (pin "A") (pinfunction "A_A") (pintype "passive"))
      (node (ref "D14") (pin "A") (pinfunction "A_A") (pintype "passive"))
      (node (ref "D15") (pin "A") (pinfunction "A_A") (pintype "passive"))
      (node (ref "D16") (pin "A") (pinfunction "A_A") (pintype "passive"))
      (node (ref "D17") (pin "A") (pinfunction "A_A") (pintype "passive"))
      (node (ref "D19") (pin "A") (pinfunction "A_A") (pintype "passive"))
      (node (ref "D2") (pin "A") (pinfunction "A_A") (pintype "passive"))
      (node (ref "D20") (pin "A") (pinfunction "A_A") (pintype "passive"))
      (node (ref "D24") (pin "A") (pinfunction "A_A") (pintype "passive"))
      (node (ref "D25") (pin "A") (pinfunction "A_A") (pintype "passive"))
      (node (ref "D27") (pin "A") (pinfunction "A_A") (pintype "passive"))
      (node (ref "D28") (pin "A") (pinfunction "A_A") (pintype "passive"))
      (node (ref "D29") (pin "A") (pinfunction "A_A") (pintype "passive"))
      (node (ref "D3") (pin "A") (pinfunction "A_A") (pintype "passive"))
      (node (ref "D4") (pin "A") (pinfunction "A_A") (pintype "passive"))
      (node (ref "D5") (pin "A") (pinfunction "A_A") (pintype "passive"))
      (node (ref "D6") (pin "A") (pinfunction "A_A") (pintype "passive"))
      (node (ref "D7") (pin "A") (pinfunction "A_A") (pintype "passive"))
      (node (ref "D8") (pin "A") (pinfunction "A_A") (pintype "passive"))
      (node (ref "D9") (pin "A") (pinfunction "A_A") (pintype "passive"))
      (node (ref "DISPLAY") (pin "1") (pinfunction "1_1") (pintype "passive"))
      (node (ref "F2") (pin "1") (pinfunction "1_1") (pintype "passive"))
      (node (ref "IC11") (pin "10") (pinfunction "SCL_10") (pintype "input"))
      (node (ref "IC11") (pin "13") (pinfunction "G_13") (pintype "input"))
      (node (ref "IC11") (pin "8") (pinfunction "GND_8") (pintype "power_in"))
      (node (ref "IC12") (pin "10") (pinfunction "SCL_10") (pintype "input"))
      (node (ref "IC12") (pin "13") (pinfunction "G_13") (pintype "input"))
      (node (ref "IC12") (pin "8") (pinfunction "GND_8") (pintype "power_in"))
      (node (ref "IC2") (pin "4") (pinfunction "V-_4") (pintype "power_in"))
      (node (ref "IC3") (pin "12") (pinfunction "VSS_12") (pintype "power_in"))
      (node (ref "IC3") (pin "15") (pinfunction "INH_15") (pintype "input"))
      (node (ref "IC8") (pin "1") (pinfunction "A0_1") (pintype "input"))
      (node (ref "IC8") (pin "2") (pinfunction "A1_2") (pintype "input"))
      (node (ref "IC8") (pin "3") (pinfunction "A2_3") (pintype "input"))
      (node (ref "IC8") (pin "4") (pinfunction "GND_4") (pintype "power_in"))
      (node (ref "IC9") (pin "4") (pinfunction "V-_4") (pintype "power_in"))
      (node (ref "P3") (pin "1") (pinfunction "1_1") (pintype "passive"))
      (node (ref "P3") (pin "2") (pinfunction "2_2") (pintype "passive"))
      (node (ref "P3") (pin "3") (pinfunction "3_3") (pintype "passive"))
      (node (ref "P3") (pin "4") (pinfunction "4_4") (pintype "passive"))
      (node (ref "PROG") (pin "1") (pinfunction "1_1") (pintype "passive"))
      (node (ref "Q10") (pin "E") (pinfunction "E_E") (pintype "passive"))
      (node (ref "Q12") (pin "C") (pinfunction "C_C") (pintype "passive"))
      (node (ref "Q13") (pin "C") (pinfunction "C_C") (pintype "passive"))
      (node (ref "Q15") (pin "E") (pinfunction "E_E") (pintype "passive"))
      (node (ref "Q16") (pin "E") (pinfunction "E_E") (pintype "passive"))
      (node (ref "Q19") (pin "C") (pinfunction "C_C") (pintype "passive"))
      (node (ref "Q2") (pin "E") (pinfunction "E_E") (pintype "passive"))
      (node (ref "Q22") (pin "C") (pinfunction "C_C") (pintype "passive"))
      (node (ref "Q25") (pin "C") (pinfunction "C_C") (pintype "passive"))
      (node (ref "Q26") (pin "E") (pinfunction "E_E") (pintype "passive"))
      (node (ref "Q4") (pin "E") (pinfunction "E_E") (pintype "passive"))
      (node (ref "Q5") (pin "C") (pinfunction "C_C") (pintype "passive"))
      (node (ref "Q9") (pin "E") (pinfunction "E_E") (pintype "passive"))
      (node (ref "R2") (pin "1") (pinfunction "1_1") (pintype "passive"))
      (node (ref "R26") (pin "2") (pinfunction "2_2") (pintype "passive"))
      (node (ref "R29") (pin "2") (pinfunction "2_2") (pintype "passive"))
      (node (ref "R8") (pin "1") (pinfunction "1_1") (pintype "passive"))
      (node (ref "SJ1") (pin "2") (pinfunction "2_2") (pintype "passive"))
      (node (ref "SV1") (pin "1") (pinfunction "1_1") (pintype "passive"))
      (node (ref "SV2") (pin "1") (pinfunction "1_1") (pintype "passive"))
      (node (ref "SV3") (pin "1") (pinfunction "1_1") (pintype "passive"))
      (node (ref "SV3") (pin "2") (pinfunction "2_2") (pintype "passive"))
      (node (ref "U$2") (pin "GND_1") (pinfunction "GND_GND_1") (pintype "bidirectional"))
      (node (ref "U$2") (pin "GND_2") (pinfunction "GND_GND_2") (pintype "bidirectional"))
      (node (ref "U$2") (pin "GND_3") (pinfunction "GND_GND_3") (pintype "power_in"))
      (node (ref "X2") (pin "4") (pinfunction "4_4") (pintype "passive"))
    )
    (net (code "51") (name "GND2") (class "Default")
      (node (ref "F2") (pin "2") (pinfunction "2_2") (pintype "passive"))
      (node (ref "Q1") (pin "S") (pinfunction "S_S") (pintype "passive"))
      (node (ref "Q14") (pin "S") (pinfunction "S_S") (pintype "passive"))
      (node (ref "Q20") (pin "S") (pinfunction "S_S") (pintype "passive"))
      (node (ref "Q23") (pin "S") (pinfunction "S_S") (pintype "passive"))
      (node (ref "Q6") (pin "S") (pinfunction "S_S") (pintype "passive"))
      (node (ref "Q7") (pin "S") (pinfunction "S_S") (pintype "passive"))
    )
    (net (code "52") (name "IAC_A") (class "Default")
      (node (ref "SV4") (pin "4") (pinfunction "4_4") (pintype "passive"))
    )
    (net (code "53") (name "IAC_B") (class "Default")
      (node (ref "SV4") (pin "3") (pinfunction "3_3") (pintype "passive"))
    )
    (net (code "54") (name "IAC_C") (class "Default")
      (node (ref "SV4") (pin "2") (pinfunction "2_2") (pintype "passive"))
    )
    (net (code "55") (name "IAC_D") (class "Default")
      (node (ref "SV4") (pin "1") (pinfunction "1_1") (pintype "passive"))
    )
    (net (code "56") (name "INY1") (class "Default")
      (node (ref "D25") (pin "C") (pinfunction "C_C") (pintype "passive"))
      (node (ref "P1") (pin "1") (pinfunction "1_1") (pintype "passive"))
      (node (ref "Q6") (pin "D") (pinfunction "D_D") (pintype "passive"))
    )
    (net (code "57") (name "INY2") (class "Default")
      (node (ref "D1") (pin "C") (pinfunction "C_C") (pintype "passive"))
      (node (ref "P1") (pin "2") (pinfunction "2_2") (pintype "passive"))
      (node (ref "Q1") (pin "D") (pinfunction "D_D") (pintype "passive"))
    )
    (net (code "58") (name "INY3") (class "Default")
      (node (ref "D4") (pin "C") (pinfunction "C_C") (pintype "passive"))
      (node (ref "P1") (pin "3") (pinfunction "3_3") (pintype "passive"))
      (node (ref "Q7") (pin "D") (pinfunction "D_D") (pintype "passive"))
    )
    (net (code "59") (name "INY4") (class "Default")
      (node (ref "D6") (pin "C") (pinfunction "C_C") (pintype "passive"))
      (node (ref "P1") (pin "4") (pinfunction "4_4") (pintype "passive"))
      (node (ref "Q14") (pin "D") (pinfunction "D_D") (pintype "passive"))
    )
    (net (code "60") (name "INY5") (class "Default")
      (node (ref "D7") (pin "C") (pinfunction "C_C") (pintype "passive"))
      (node (ref "P1") (pin "5") (pinfunction "5_5") (pintype "passive"))
      (node (ref "Q20") (pin "D") (pinfunction "D_D") (pintype "passive"))
    )
    (net (code "61") (name "INY6") (class "Default")
      (node (ref "D16") (pin "C") (pinfunction "C_C") (pintype "passive"))
      (node (ref "P1") (pin "6") (pinfunction "6_6") (pintype "passive"))
      (node (ref "Q23") (pin "D") (pinfunction "D_D") (pintype "passive"))
    )
    (net (code "62") (name "INYL1A") (class "Default")
      (node (ref "R31") (pin "2") (pinfunction "2_2") (pintype "passive"))
    )
    (net (code "63") (name "INYL2A") (class "Default")
      (node (ref "R33") (pin "2") (pinfunction "2_2") (pintype "passive"))
    )
    (net (code "64") (name "INYL3A") (class "Default")
      (node (ref "R43") (pin "2") (pinfunction "2_2") (pintype "passive"))
    )
    (net (code "65") (name "INYL4A") (class "Default")
      (node (ref "R45") (pin "2") (pinfunction "2_2") (pintype "passive"))
    )
    (net (code "66") (name "INYL5A") (class "Default")
      (node (ref "R47") (pin "2") (pinfunction "2_2") (pintype "passive"))
    )
    (net (code "67") (name "INYL6A") (class "Default")
      (node (ref "R49") (pin "2") (pinfunction "2_2") (pintype "passive"))
    )
    (net (code "68") (name "L1") (class "Default")
      (node (ref "R9") (pin "1") (pinfunction "1_1") (pintype "passive"))
    )
    (net (code "69") (name "L2") (class "Default")
      (node (ref "R10") (pin "1") (pinfunction "1_1") (pintype "passive"))
    )
    (net (code "70") (name "L3") (class "Default")
      (node (ref "R11") (pin "1") (pinfunction "1_1") (pintype "passive"))
    )
    (net (code "71") (name "L4") (class "Default")
      (node (ref "R12") (pin "1") (pinfunction "1_1") (pintype "passive"))
    )
    (net (code "72") (name "L5") (class "Default")
      (node (ref "R14") (pin "1") (pinfunction "1_1") (pintype "passive"))
      (node (ref "U$2") (pin "PA_5") (pinfunction "PA_5_PA_5") (pintype "bidirectional"))
    )
    (net (code "73") (name "LAMB0") (class "Default")
      (node (ref "R25") (pin "1") (pinfunction "1_1") (pintype "passive"))
    )
    (net (code "74") (name "LAMB0OUT") (class "Default")
      (node (ref "C17") (pin "1") (pinfunction "1_1") (pintype "passive"))
      (node (ref "IC3") (pin "23") (pinfunction "X8_23") (pintype "input"))
      (node (ref "IC9") (pin "1") (pinfunction "OUT_1") (pintype "output"))
      (node (ref "R27") (pin "2") (pinfunction "2_2") (pintype "passive"))
    )
    (net (code "75") (name "LAMB1") (class "Default")
      (node (ref "R28") (pin "1") (pinfunction "1_1") (pintype "passive"))
    )
    (net (code "76") (name "LAMB1OUT") (class "Default")
      (node (ref "C19") (pin "1") (pinfunction "1_1") (pintype "passive"))
      (node (ref "IC3") (pin "22") (pinfunction "X9_22") (pintype "input"))
      (node (ref "IC9") (pin "7") (pinfunction "OUT_7") (pintype "output"))
      (node (ref "R30") (pin "2") (pinfunction "2_2") (pintype "passive"))
    )
    (net (code "77") (name "LED1") (class "Default")
      (node (ref "Q2") (pin "C") (pinfunction "C_C") (pintype "passive"))
    )
    (net (code "78") (name "LED1A") (class "Default")
      (node (ref "R3") (pin "1") (pinfunction "1_1") (pintype "passive"))
    )
    (net (code "79") (name "M1") (class "Default")
      (node (ref "IC11") (pin "15") (pinfunction "QA_15") (pintype "tri_state"))
      (node (ref "SV3") (pin "6") (pinfunction "6_6") (pintype "passive"))
    )
    (net (code "80") (name "M2") (class "Default")
      (node (ref "IC11") (pin "1") (pinfunction "QB_1") (pintype "tri_state"))
      (node (ref "SV3") (pin "5") (pinfunction "5_5") (pintype "passive"))
    )
    (net (code "81") (name "M3") (class "Default")
      (node (ref "IC11") (pin "2") (pinfunction "QC_2") (pintype "tri_state"))
      (node (ref "SV3") (pin "4") (pinfunction "4_4") (pintype "passive"))
    )
    (net (code "82") (name "M4") (class "Default")
      (node (ref "IC11") (pin "3") (pinfunction "QD_3") (pintype "tri_state"))
      (node (ref "SV3") (pin "3") (pinfunction "3_3") (pintype "passive"))
    )
    (net (code "84") (name "MISO") (class "Default")
      (node (ref "U$2") (pin "PB_6") (pinfunction "PB_6_PB_6") (pintype "bidirectional"))
    )
    (net (code "85") (name "MOSI") (class "Default")
      (node (ref "U$2") (pin "PB_7") (pinfunction "PB_7_PB_7") (pintype "bidirectional"))
    )
    (net (code "86") (name "Net-(D18-PadA)") (class "Default")
      (node (ref "D18") (pin "A") (pinfunction "A_A") (pintype "passive"))
      (node (ref "PROG") (pin "4") (pinfunction "4_4") (pintype "passive"))
    )
    (net (code "87") (name "Net-(IC2A-+IN)") (class "Default")
      (node (ref "IC2") (pin "3") (pinfunction "+IN_3") (pintype "input"))
      (node (ref "R1") (pin "2") (pinfunction "2_2") (pintype "passive"))
      (node (ref "R2") (pin "2") (pinfunction "2_2") (pintype "passive"))
    )
    (net (code "88") (name "Net-(IC8-WP)") (class "Default")
      (node (ref "IC8") (pin "7") (pinfunction "WP_7") (pintype "input"))
      (node (ref "SJ1") (pin "1") (pinfunction "1_1") (pintype "passive"))
    )
    (net (code "89") (name "Net-(IC9A-+IN)") (class "Default")
      (node (ref "C16") (pin "1") (pinfunction "1_1") (pintype "passive"))
      (node (ref "IC9") (pin "3") (pinfunction "+IN_3") (pintype "input"))
      (node (ref "R25") (pin "2") (pinfunction "2_2") (pintype "passive"))
    )
    (net (code "90") (name "Net-(IC9A--IN)") (class "Default")
      (node (ref "IC9") (pin "2") (pinfunction "-IN_2") (pintype "input"))
      (node (ref "R26") (pin "1") (pinfunction "1_1") (pintype "passive"))
      (node (ref "R27") (pin "1") (pinfunction "1_1") (pintype "passive"))
    )
    (net (code "91") (name "Net-(IC9B-+IN)") (class "Default")
      (node (ref "C18") (pin "1") (pinfunction "1_1") (pintype "passive"))
      (node (ref "IC9") (pin "5") (pinfunction "+IN_5") (pintype "input"))
      (node (ref "R28") (pin "2") (pinfunction "2_2") (pintype "passive"))
    )
    (net (code "92") (name "Net-(IC9B--IN)") (class "Default")
      (node (ref "IC9") (pin "6") (pinfunction "-IN_6") (pintype "input"))
      (node (ref "R29") (pin "1") (pinfunction "1_1") (pintype "passive"))
      (node (ref "R30") (pin "1") (pinfunction "1_1") (pintype "passive"))
    )
    (net (code "93") (name "Net-(IC11A-QH*)") (class "Default")
      (node (ref "IC11") (pin "9") (pinfunction "QH*_9") (pintype "tri_state"))
      (node (ref "IC12") (pin "14") (pinfunction "SER_14") (pintype "input"))
    )
    (net (code "94") (name "Net-(LED1-C)") (class "Default")
      (node (ref "LED1") (pin "K") (pinfunction "C_K") (pintype "passive"))
      (node (ref "R9") (pin "2") (pinfunction "2_2") (pintype "passive"))
    )
    (net (code "95") (name "Net-(LED2-C)") (class "Default")
      (node (ref "LED2") (pin "K") (pinfunction "C_K") (pintype "passive"))
      (node (ref "R10") (pin "2") (pinfunction "2_2") (pintype "passive"))
    )
    (net (code "96") (name "Net-(LED3-C)") (class "Default")
      (node (ref "LED3") (pin "K") (pinfunction "C_K") (pintype "passive"))
      (node (ref "R11") (pin "2") (pinfunction "2_2") (pintype "passive"))
    )
    (net (code "97") (name "Net-(LED4-C)") (class "Default")
      (node (ref "LED4") (pin "K") (pinfunction "C_K") (pintype "passive"))
      (node (ref "R12") (pin "2") (pinfunction "2_2") (pintype "passive"))
    )
    (net (code "98") (name "Net-(LED5-C)") (class "Default")
      (node (ref "LED5") (pin "K") (pinfunction "C_K") (pintype "passive"))
      (node (ref "R14") (pin "2") (pinfunction "2_2") (pintype "passive"))
    )
    (net (code "99") (name "Net-(Q1-PadG)") (class "Default")
      (node (ref "Q1") (pin "G") (pinfunction "G_G") (pintype "passive"))
      (node (ref "R34") (pin "1") (pinfunction "1_1") (pintype "passive"))
    )
    (net (code "100") (name "Net-(Q2-PadB)") (class "Default")
      (node (ref "Q2") (pin "B") (pinfunction "B_B") (pintype "passive"))
      (node (ref "R3") (pin "2") (pinfunction "2_2") (pintype "passive"))
    )
    (net (code "101") (name "Net-(Q3-PadB)") (class "Default")
      (node (ref "Q3") (pin "B") (pinfunction "B_B") (pintype "passive"))
      (node (ref "Q5") (pin "B") (pinfunction "B_B") (pintype "passive"))
      (node (ref "R33") (pin "1") (pinfunction "1_1") (pintype "passive"))
    )
    (net (code "102") (name "Net-(Q3-PadE)") (class "Default")
      (node (ref "Q3") (pin "E") (pinfunction "E_E") (pintype "passive"))
      (node (ref "Q5") (pin "E") (pinfunction "E_E") (pintype "passive"))
      (node (ref "R34") (pin "2") (pinfunction "2_2") (pintype "passive"))
    )
    (net (code "103") (name "Net-(Q4-PadB)") (class "Default")
      (node (ref "Q4") (pin "B") (pinfunction "B_B") (pintype "passive"))
      (node (ref "R51") (pin "2") (pinfunction "2_2") (pintype "passive"))
    )
    (net (code "104") (name "Net-(Q6-PadG)") (class "Default")
      (node (ref "Q6") (pin "G") (pinfunction "G_G") (pintype "passive"))
      (node (ref "R32") (pin "1") (pinfunction "1_1") (pintype "passive"))
    )
    (net (code "105") (name "Net-(Q7-PadG)") (class "Default")
      (node (ref "Q7") (pin "G") (pinfunction "G_G") (pintype "passive"))
      (node (ref "R44") (pin "1") (pinfunction "1_1") (pintype "passive"))
    )
    (net (code "106") (name "Net-(Q9-PadB)") (class "Default")
      (node (ref "Q9") (pin "B") (pinfunction "B_B") (pintype "passive"))
      (node (ref "R17") (pin "2") (pinfunction "2_2") (pintype "passive"))
    )
    (net (code "107") (name "Net-(Q10-PadB)") (class "Default")
      (node (ref "Q10") (pin "B") (pinfunction "B_B") (pintype "passive"))
      (node (ref "R20") (pin "2") (pinfunction "2_2") (pintype "passive"))
    )
    (net (code "108") (name "Net-(Q11-PadB)") (class "Default")
      (node (ref "Q11") (pin "B") (pinfunction "B_B") (pintype "passive"))
      (node (ref "Q12") (pin "B") (pinfunction "B_B") (pintype "passive"))
      (node (ref "R31") (pin "1") (pinfunction "1_1") (pintype "passive"))
    )
    (net (code "109") (name "Net-(Q11-PadE)") (class "Default")
      (node (ref "Q11") (pin "E") (pinfunction "E_E") (pintype "passive"))
      (node (ref "Q12") (pin "E") (pinfunction "E_E") (pintype "passive"))
      (node (ref "R32") (pin "2") (pinfunction "2_2") (pintype "passive"))
    )
    (net (code "110") (name "Net-(Q13-PadB)") (class "Default")
      (node (ref "Q13") (pin "B") (pinfunction "B_B") (pintype "passive"))
      (node (ref "Q8") (pin "B") (pinfunction "B_B") (pintype "passive"))
      (node (ref "R43") (pin "1") (pinfunction "1_1") (pintype "passive"))
    )
    (net (code "111") (name "Net-(Q13-PadE)") (class "Default")
      (node (ref "Q13") (pin "E") (pinfunction "E_E") (pintype "passive"))
      (node (ref "Q8") (pin "E") (pinfunction "E_E") (pintype "passive"))
      (node (ref "R44") (pin "2") (pinfunction "2_2") (pintype "passive"))
    )
    (net (code "112") (name "Net-(Q14-PadG)") (class "Default")
      (node (ref "Q14") (pin "G") (pinfunction "G_G") (pintype "passive"))
      (node (ref "R46") (pin "1") (pinfunction "1_1") (pintype "passive"))
    )
    (net (code "113") (name "Net-(Q15-PadB)") (class "Default")
      (node (ref "Q15") (pin "B") (pinfunction "B_B") (pintype "passive"))
      (node (ref "R23") (pin "2") (pinfunction "2_2") (pintype "passive"))
    )
    (net (code "114") (name "Net-(Q16-PadB)") (class "Default")
      (node (ref "Q16") (pin "B") (pinfunction "B_B") (pintype "passive"))
      (node (ref "R21") (pin "2") (pinfunction "2_2") (pintype "passive"))
    )
    (net (code "115") (name "Net-(Q18-PadB)") (class "Default")
      (node (ref "Q18") (pin "B") (pinfunction "B_B") (pintype "passive"))
      (node (ref "Q19") (pin "B") (pinfunction "B_B") (pintype "passive"))
      (node (ref "R45") (pin "1") (pinfunction "1_1") (pintype "passive"))
    )
    (net (code "116") (name "Net-(Q18-PadE)") (class "Default")
      (node (ref "Q18") (pin "E") (pinfunction "E_E") (pintype "passive"))
      (node (ref "Q19") (pin "E") (pinfunction "E_E") (pintype "passive"))
      (node (ref "R46") (pin "2") (pinfunction "2_2") (pintype "passive"))
    )
    (net (code "117") (name "Net-(Q20-PadG)") (class "Default")
      (node (ref "Q20") (pin "G") (pinfunction "G_G") (pintype "passive"))
      (node (ref "R48") (pin "1") (pinfunction "1_1") (pintype "passive"))
    )
    (net (code "118") (name "Net-(Q21-PadB)") (class "Default")
      (node (ref "Q21") (pin "B") (pinfunction "B_B") (pintype "passive"))
      (node (ref "Q22") (pin "B") (pinfunction "B_B") (pintype "passive"))
      (node (ref "R47") (pin "1") (pinfunction "1_1") (pintype "passive"))
    )
    (net (code "119") (name "Net-(Q21-PadE)") (class "Default")
      (node (ref "Q21") (pin "E") (pinfunction "E_E") (pintype "passive"))
      (node (ref "Q22") (pin "E") (pinfunction "E_E") (pintype "passive"))
      (node (ref "R48") (pin "2") (pinfunction "2_2") (pintype "passive"))
    )
    (net (code "120") (name "Net-(Q23-PadG)") (class "Default")
      (node (ref "Q23") (pin "G") (pinfunction "G_G") (pintype "passive"))
      (node (ref "R50") (pin "1") (pinfunction "1_1") (pintype "passive"))
    )
    (net (code "121") (name "Net-(Q24-PadB)") (class "Default")
      (node (ref "Q24") (pin "B") (pinfunction "B_B") (pintype "passive"))
      (node (ref "Q25") (pin "B") (pinfunction "B_B") (pintype "passive"))
      (node (ref "R49") (pin "1") (pinfunction "1_1") (pintype "passive"))
    )
    (net (code "122") (name "Net-(Q24-PadE)") (class "Default")
      (node (ref "Q24") (pin "E") (pinfunction "E_E") (pintype "passive"))
      (node (ref "Q25") (pin "E") (pinfunction "E_E") (pintype "passive"))
      (node (ref "R50") (pin "2") (pinfunction "2_2") (pintype "passive"))
    )
    (net (code "123") (name "Net-(Q26-PadB)") (class "Default")
      (node (ref "Q26") (pin "B") (pinfunction "B_B") (pintype "passive"))
      (node (ref "R16") (pin "2") (pinfunction "2_2") (pintype "passive"))
    )
    (net (code "124") (name "PWM") (class "Default")
      (node (ref "SV4") (pin "7") (pinfunction "7_7") (pintype "passive"))
    )
    (net (code "125") (name "RCK") (class "Default")
      (node (ref "IC11") (pin "12") (pinfunction "RCK_12") (pintype "input"))
      (node (ref "IC12") (pin "12") (pinfunction "RCK_12") (pintype "input"))
    )
    (net (code "126") (name "RL1") (class "Default")
      (node (ref "IC11") (pin "4") (pinfunction "QE_4") (pintype "tri_state"))
      (node (ref "R16") (pin "1") (pinfunction "1_1") (pintype "passive"))
    )
    (net (code "127") (name "RL1IN") (class "Default")
      (node (ref "D9") (pin "C") (pinfunction "C_C") (pintype "passive"))
      (node (ref "J1") (pin "1") (pinfunction "1_1") (pintype "passive"))
      (node (ref "Q26") (pin "C") (pinfunction "C_C") (pintype "passive"))
    )
    (net (code "128") (name "RL2") (class "Default")
      (node (ref "IC11") (pin "5") (pinfunction "QF_5") (pintype "tri_state"))
      (node (ref "R17") (pin "1") (pinfunction "1_1") (pintype "passive"))
    )
    (net (code "129") (name "RL2IN") (class "Default")
      (node (ref "D12") (pin "C") (pinfunction "C_C") (pintype "passive"))
      (node (ref "J1") (pin "2") (pinfunction "2_2") (pintype "passive"))
      (node (ref "Q9") (pin "C") (pinfunction "C_C") (pintype "passive"))
    )
    (net (code "130") (name "RL3") (class "Default")
      (node (ref "IC11") (pin "6") (pinfunction "QG_6") (pintype "tri_state"))
      (node (ref "R20") (pin "1") (pinfunction "1_1") (pintype "passive"))
    )
    (net (code "131") (name "RL3IN") (class "Default")
      (node (ref "D13") (pin "C") (pinfunction "C_C") (pintype "passive"))
      (node (ref "J1") (pin "3") (pinfunction "3_3") (pintype "passive"))
      (node (ref "Q10") (pin "C") (pinfunction "C_C") (pintype "passive"))
    )
    (net (code "132") (name "RL4") (class "Default")
      (node (ref "IC11") (pin "7") (pinfunction "QH_7") (pintype "tri_state"))
      (node (ref "R23") (pin "1") (pinfunction "1_1") (pintype "passive"))
    )
    (net (code "133") (name "RL4IN") (class "Default")
      (node (ref "D14") (pin "C") (pinfunction "C_C") (pintype "passive"))
      (node (ref "J1") (pin "4") (pinfunction "4_4") (pintype "passive"))
      (node (ref "Q15") (pin "C") (pinfunction "C_C") (pintype "passive"))
    )
    (net (code "134") (name "RL5") (class "Default")
      (node (ref "IC12") (pin "15") (pinfunction "QA_15") (pintype "tri_state"))
      (node (ref "R21") (pin "1") (pinfunction "1_1") (pintype "passive"))
    )
    (net (code "135") (name "RL5IN") (class "Default")
      (node (ref "D15") (pin "C") (pinfunction "C_C") (pintype "passive"))
      (node (ref "J1") (pin "5") (pinfunction "5_5") (pintype "passive"))
      (node (ref "Q16") (pin "C") (pinfunction "C_C") (pintype "passive"))
    )
    (net (code "136") (name "RL6") (class "Default")
      (node (ref "R51") (pin "1") (pinfunction "1_1") (pintype "passive"))
    )
    (net (code "137") (name "RL6IN") (class "Default")
      (node (ref "D20") (pin "C") (pinfunction "C_C") (pintype "passive"))
      (node (ref "J1") (pin "6") (pinfunction "6_6") (pintype "passive"))
      (node (ref "Q4") (pin "C") (pinfunction "C_C") (pintype "passive"))
    )
    (net (code "138") (name "RX") (class "Default")
      (node (ref "PROG") (pin "3") (pinfunction "3_3") (pintype "passive"))
      (node (ref "U$2") (pin "PA_9") (pinfunction "PA_9_PA_9") (pintype "bidirectional"))
    )
    (net (code "139") (name "SCK") (class "Default")
      (node (ref "U$2") (pin "PB_5") (pinfunction "PB_5_PB_5") (pintype "bidirectional"))
    )
    (net (code "140") (name "SCK2") (class "Default")
      (node (ref "IC11") (pin "11") (pinfunction "SCK_11") (pintype "input"))
      (node (ref "IC12") (pin "11") (pinfunction "SCK_11") (pintype "input"))
    )
    (net (code "141") (name "SCL") (class "Default")
      (node (ref "DISPLAY") (pin "4") (pinfunction "4_4") (pintype "passive"))
      (node (ref "IC8") (pin "6") (pinfunction "SCL_6") (pintype "input"))
      (node (ref "U$2") (pin "PB_10") (pinfunction "PB_10_PB_10") (pintype "bidirectional"))
    )
    (net (code "142") (name "SDA") (class "Default")
      (node (ref "DISPLAY") (pin "3") (pinfunction "3_3") (pintype "passive"))
      (node (ref "IC8") (pin "5") (pinfunction "SDA_5") (pintype "bidirectional"))
      (node (ref "U$2") (pin "PB_11") (pinfunction "PB_11_PB_11") (pintype "bidirectional"))
    )
    (net (code "143") (name "SER") (class "Default")
      (node (ref "IC11") (pin "14") (pinfunction "SER_14") (pintype "input"))
    )
    (net (code "144") (name "SS") (class "Default")
      (node (ref "U$2") (pin "PB_4") (pinfunction "PB_4_PB_4") (pintype "bidirectional"))
    )
    (net (code "148") (name "TPSM_A") (class "Default")
      (node (ref "SV4") (pin "6") (pinfunction "6_6") (pintype "passive"))
    )
    (net (code "149") (name "TPSM_B") (class "Default")
      (node (ref "SV4") (pin "5") (pinfunction "5_5") (pintype "passive"))
    )
    (net (code "150") (name "TX") (class "Default")
      (node (ref "PROG") (pin "2") (pinfunction "2_2") (pintype "passive"))
      (node (ref "U$2") (pin "PA_10") (pinfunction "PA_10_PA_10") (pintype "bidirectional"))
    )
    (net (code "151") (name "VBAT") (class "Default")
      (node (ref "D27") (pin "C") (pinfunction "C_C") (pintype "passive"))
      (node (ref "IC3") (pin "21") (pinfunction "X10_21") (pintype "input"))
      (node (ref "R7") (pin "1") (pinfunction "1_1") (pintype "passive"))
      (node (ref "R8") (pin "2") (pinfunction "2_2") (pintype "passive"))
    )
    (net (code "152") (name "unconnected-(D13-PadA)") (class "Default")
      (node (ref "D13") (pin "A") (pinfunction "A_A") (pintype "passive"))
    )
    (net (code "153") (name "unconnected-(IC12A-QH*-Pad9)") (class "Default")
      (node (ref "IC12") (pin "9") (pinfunction "QH*_9") (pintype "tri_state"))
    )
    (net (code "154") (name "unconnected-(J2-Pad1)") (class "Default")
      (node (ref "J2") (pin "1") (pinfunction "1_1") (pintype "passive"))
    )
    (net (code "155") (name "unconnected-(J2-Pad2)") (class "Default")
      (node (ref "J2") (pin "2") (pinfunction "2_2") (pintype "passive"))
    )
    (net (code "156") (name "unconnected-(J2-Pad3)") (class "Default")
      (node (ref "J2") (pin "3") (pinfunction "3_3") (pintype "passive"))
    )
    (net (code "157") (name "unconnected-(J2-Pad4)") (class "Default")
      (node (ref "J2") (pin "4") (pinfunction "4_4") (pintype "passive"))
    )
    (net (code "158") (name "unconnected-(J2-Pad5)") (class "Default")
      (node (ref "J2") (pin "5") (pinfunction "5_5") (pintype "passive"))
    )
    (net (code "159") (name "unconnected-(J2-Pad6)") (class "Default")
      (node (ref "J2") (pin "6") (pinfunction "6_6") (pintype "passive"))
    )
    (net (code "160") (name "unconnected-(R15-Pad1)") (class "Default")
      (node (ref "R15") (pin "1") (pinfunction "1_1") (pintype "passive"))
    )
    (net (code "161") (name "unconnected-(R15-Pad2)") (class "Default")
      (node (ref "R15") (pin "2") (pinfunction "2_2") (pintype "passive"))
    )
    (net (code "162") (name "unconnected-(U$2-3.3V-Pad3.3V_2)") (class "Default")
      (node (ref "U$2") (pin "3.3V_2") (pinfunction "3.3V_3.3V_2") (pintype "bidirectional"))
    )
    (net (code "163") (name "unconnected-(U$2-PadPA_1)") (class "Default")
      (node (ref "U$2") (pin "PA_1") (pinfunction "PA_1_PA_1") (pintype "bidirectional"))
    )
    (net (code "164") (name "unconnected-(U$2-PadPA_2)") (class "Default")
      (node (ref "U$2") (pin "PA_2") (pinfunction "PA_2_PA_2") (pintype "bidirectional"))
    )
    (net (code "165") (name "unconnected-(U$2-PadPA_3)") (class "Default")
      (node (ref "U$2") (pin "PA_3") (pinfunction "PA_3_PA_3") (pintype "bidirectional"))
    )
    (net (code "166") (name "unconnected-(U$2-PadPA_4)") (class "Default")
      (node (ref "U$2") (pin "PA_4") (pinfunction "PA_4_PA_4") (pintype "bidirectional"))
    )
    (net (code "167") (name "unconnected-(U$2-PadPA_8)") (class "Default")
      (node (ref "U$2") (pin "PA_8") (pinfunction "PA_8_PA_8") (pintype "bidirectional"))
    )
    (net (code "168") (name "unconnected-(U$2-PadPA_15)") (class "Default")
      (node (ref "U$2") (pin "PA_15") (pinfunction "PA_15_PA_15") (pintype "bidirectional"))
    )
    (net (code "169") (name "unconnected-(U$2-PadPB_3)") (class "Default")
      (node (ref "U$2") (pin "PB_3") (pinfunction "PB_3_PB_3") (pintype "bidirectional"))
    )
    (net (code "170") (name "unconnected-(U$2-PadPB_8)") (class "Default")
      (node (ref "U$2") (pin "PB_8") (pinfunction "PB_8_PB_8") (pintype "bidirectional"))
    )
    (net (code "171") (name "unconnected-(U$2-PadPB_9)") (class "Default")
      (node (ref "U$2") (pin "PB_9") (pinfunction "PB_9_PB_9") (pintype "bidirectional"))
    )
    (net (code "172") (name "unconnected-(U$2-PadPB_12)") (class "Default")
      (node (ref "U$2") (pin "PB_12") (pinfunction "PB_12_PB_12") (pintype "bidirectional"))
    )
    (net (code "173") (name "unconnected-(U$2-PadPB_13)") (class "Default")
      (node (ref "U$2") (pin "PB_13") (pinfunction "PB_13_PB_13") (pintype "bidirectional"))
    )
    (net (code "174") (name "unconnected-(U$2-PadPB_14)") (class "Default")
      (node (ref "U$2") (pin "PB_14") (pinfunction "PB_14_PB_14") (pintype "bidirectional"))
    )
    (net (code "175") (name "unconnected-(U$2-PadPB_15)") (class "Default")
      (node (ref "U$2") (pin "PB_15") (pinfunction "PB_15_PB_15") (pintype "bidirectional"))
    )
    (net (code "176") (name "unconnected-(U$2-PadPC_13)") (class "Default")
      (node (ref "U$2") (pin "PC_13") (pinfunction "PC_13_PC_13") (pintype "bidirectional"))
    )
    (net (code "177") (name "unconnected-(U$2-PadPC_14)") (class "Default")
      (node (ref "U$2") (pin "PC_14") (pinfunction "PC_14_PC_14") (pintype "bidirectional"))
    )
    (net (code "178") (name "unconnected-(U$2-PadPC_15)") (class "Default")
      (node (ref "U$2") (pin "PC_15") (pinfunction "PC_15_PC_15") (pintype "bidirectional"))
    )
    (net (code "179") (name "unconnected-(U$2-PadRESET)") (class "Default")
      (node (ref "U$2") (pin "RESET") (pinfunction "RESET_RESET") (pintype "bidirectional"))
    )
    (net (code "180") (name "unconnected-(U$2-PadVB)") (class "Default")
      (node (ref "U$2") (pin "VB") (pinfunction "VB_VB") (pintype "bidirectional"))
    )
    (net (code "181") (name "unconnected-(X1-Pad1)") (class "Default")
      (node (ref "X1") (pin "1") (pinfunction "1_1") (pintype "passive"))
    )
    (net (code "182") (name "unconnected-(X1-Pad2)") (class "Default")
      (node (ref "X1") (pin "2") (pinfunction "2_2") (pintype "passive"))
    )
    (net (code "183") (name "unconnected-(X1-Pad3)") (class "Default")
      (node (ref "X1") (pin "3") (pinfunction "3_3") (pintype "passive"))
    )
    (net (code "184") (name "unconnected-(X1-Pad4)") (class "Default")
      (node (ref "X1") (pin "4") (pinfunction "4_4") (pintype "passive"))
    )
    (net (code "185") (name "unconnected-(X1-Pad5)") (class "Default")
      (node (ref "X1") (pin "5") (pinfunction "5_5") (pintype "passive"))
    )
    (net (code "186") (name "unconnected-(X1-Pad6)") (class "Default")
      (node (ref "X1") (pin "6") (pinfunction "6_6") (pintype "passive"))
    )
    (net (code "187") (name "unconnected-(X1-Pad7)") (class "Default")
      (node (ref "X1") (pin "7") (pinfunction "7_7") (pintype "passive"))
    )
    (net (code "188") (name "unconnected-(X1-Pad8)") (class "Default")
      (node (ref "X1") (pin "8") (pinfunction "8_8") (pintype "passive"))
    )
    (net (code "189") (name "unconnected-(X1-Pad9)") (class "Default")
      (node (ref "X1") (pin "9") (pinfunction "9_9") (pintype "passive"))
    )
    (net (code "190") (name "unconnected-(X1-Pad10)") (class "Default")
      (node (ref "X1") (pin "10") (pinfunction "10_10") (pintype "passive"))
    )
    (net (code "191") (name "unconnected-(X1-Pad11)") (class "Default")
      (node (ref "X1") (pin "11") (pinfunction "11_11") (pintype "passive"))
    )
    (net (code "192") (name "unconnected-(X1-Pad12)") (class "Default")
      (node (ref "X1") (pin "12") (pinfunction "12_12") (pintype "passive"))
    )
    (net (code "193") (name "unconnected-(X1-Pad13)") (class "Default")
      (node (ref "X1") (pin "13") (pinfunction "13_13") (pintype "passive"))
    )
    (net (code "194") (name "unconnected-(X1-Pad14)") (class "Default")
      (node (ref "X1") (pin "14") (pinfunction "14_14") (pintype "passive"))
    )
    (net (code "195") (name "unconnected-(X1-Pad15)") (class "Default")
      (node (ref "X1") (pin "15") (pinfunction "15_15") (pintype "passive"))
    )
    (net (code "196") (name "unconnected-(X1-PadG1)") (class "Default")
      (node (ref "X1") (pin "G1") (pinfunction "G1_G1") (pintype "passive"))
    )
    (net (code "197") (name "unconnected-(X1-PadG2)") (class "Default")
      (node (ref "X1") (pin "G2") (pinfunction "G2_G2") (pintype "passive"))
    )
    (net (code "198") (name "unconnected-(X3-Pad1)") (class "Default")
      (node (ref "X3") (pin "1") (pinfunction "1_1") (pintype "passive"))
    )
    (net (code "199") (name "unconnected-(X3-Pad2)") (class "Default")
      (node (ref "X3") (pin "2") (pinfunction "2_2") (pintype "passive"))
    )
    (net (code "200") (name "unconnected-(X3-Pad3)") (class "Default")
      (node (ref "X3") (pin "3") (pinfunction "3_3") (pintype "passive"))
    )
    (net (code "201") (name "unconnected-(X3-Pad4)") (class "Default")
      (node (ref "X3") (pin "4") (pinfunction "4_4") (pintype "passive"))
    )
    (net (code "202") (name "unconnected-(X3-Pad5)") (class "Default")
      (node (ref "X3") (pin "5") (pinfunction "5_5") (pintype "passive"))
    )
    (net (code "203") (name "unconnected-(X3-Pad6)") (class "Default")
      (node (ref "X3") (pin "6") (pinfunction "6_6") (pintype "passive"))
    )
    (net (code "204") (name "unconnected-(X3-Pad7)") (class "Default")
      (node (ref "X3") (pin "7") (pinfunction "7_7") (pintype "passive"))
    )
    (net (code "205") (name "unconnected-(X3-Pad8)") (class "Default")
      (node (ref "X3") (pin "8") (pinfunction "8_8") (pintype "passive"))
    )
    (net (code "206") (name "unconnected-(X3-Pad9)") (class "Default")
      (node (ref "X3") (pin "9") (pinfunction "9_9") (pintype "passive"))
    )
    (net (code "207") (name "unconnected-(X3-Pad10)") (class "Default")
      (node (ref "X3") (pin "10") (pinfunction "10_10") (pintype "passive"))
    )
    (net (code "208") (name "unconnected-(X3-Pad11)") (class "Default")
      (node (ref "X3") (pin "11") (pinfunction "11_11") (pintype "passive"))
    )
    (net (code "209") (name "unconnected-(X3-Pad12)") (class "Default")
      (node (ref "X3") (pin "12") (pinfunction "12_12") (pintype "passive"))
    )
    (net (code "210") (name "unconnected-(X3-Pad13)") (class "Default")
      (node (ref "X3") (pin "13") (pinfunction "13_13") (pintype "passive"))
    )
    (net (code "211") (name "unconnected-(X3-Pad14)") (class "Default")
      (node (ref "X3") (pin "14") (pinfunction "14_14") (pintype "passive"))
    )
    (net (code "212") (name "unconnected-(X3-Pad15)") (class "Default")
      (node (ref "X3") (pin "15") (pinfunction "15_15") (pintype "passive"))
    )
    (net (code "213") (name "unconnected-(X3-PadG1)") (class "Default")
      (node (ref "X3") (pin "G1") (pinfunction "G1_G1") (pintype "passive"))
    )
    (net (code "214") (name "unconnected-(X3-PadG2)") (class "Default")
      (node (ref "X3") (pin "G2") (pinfunction "G2_G2") (pintype "passive"))
    )
  )
)
